# oresat-proto-card.net
KiCad netlist of a schematic drawn in EAGLE
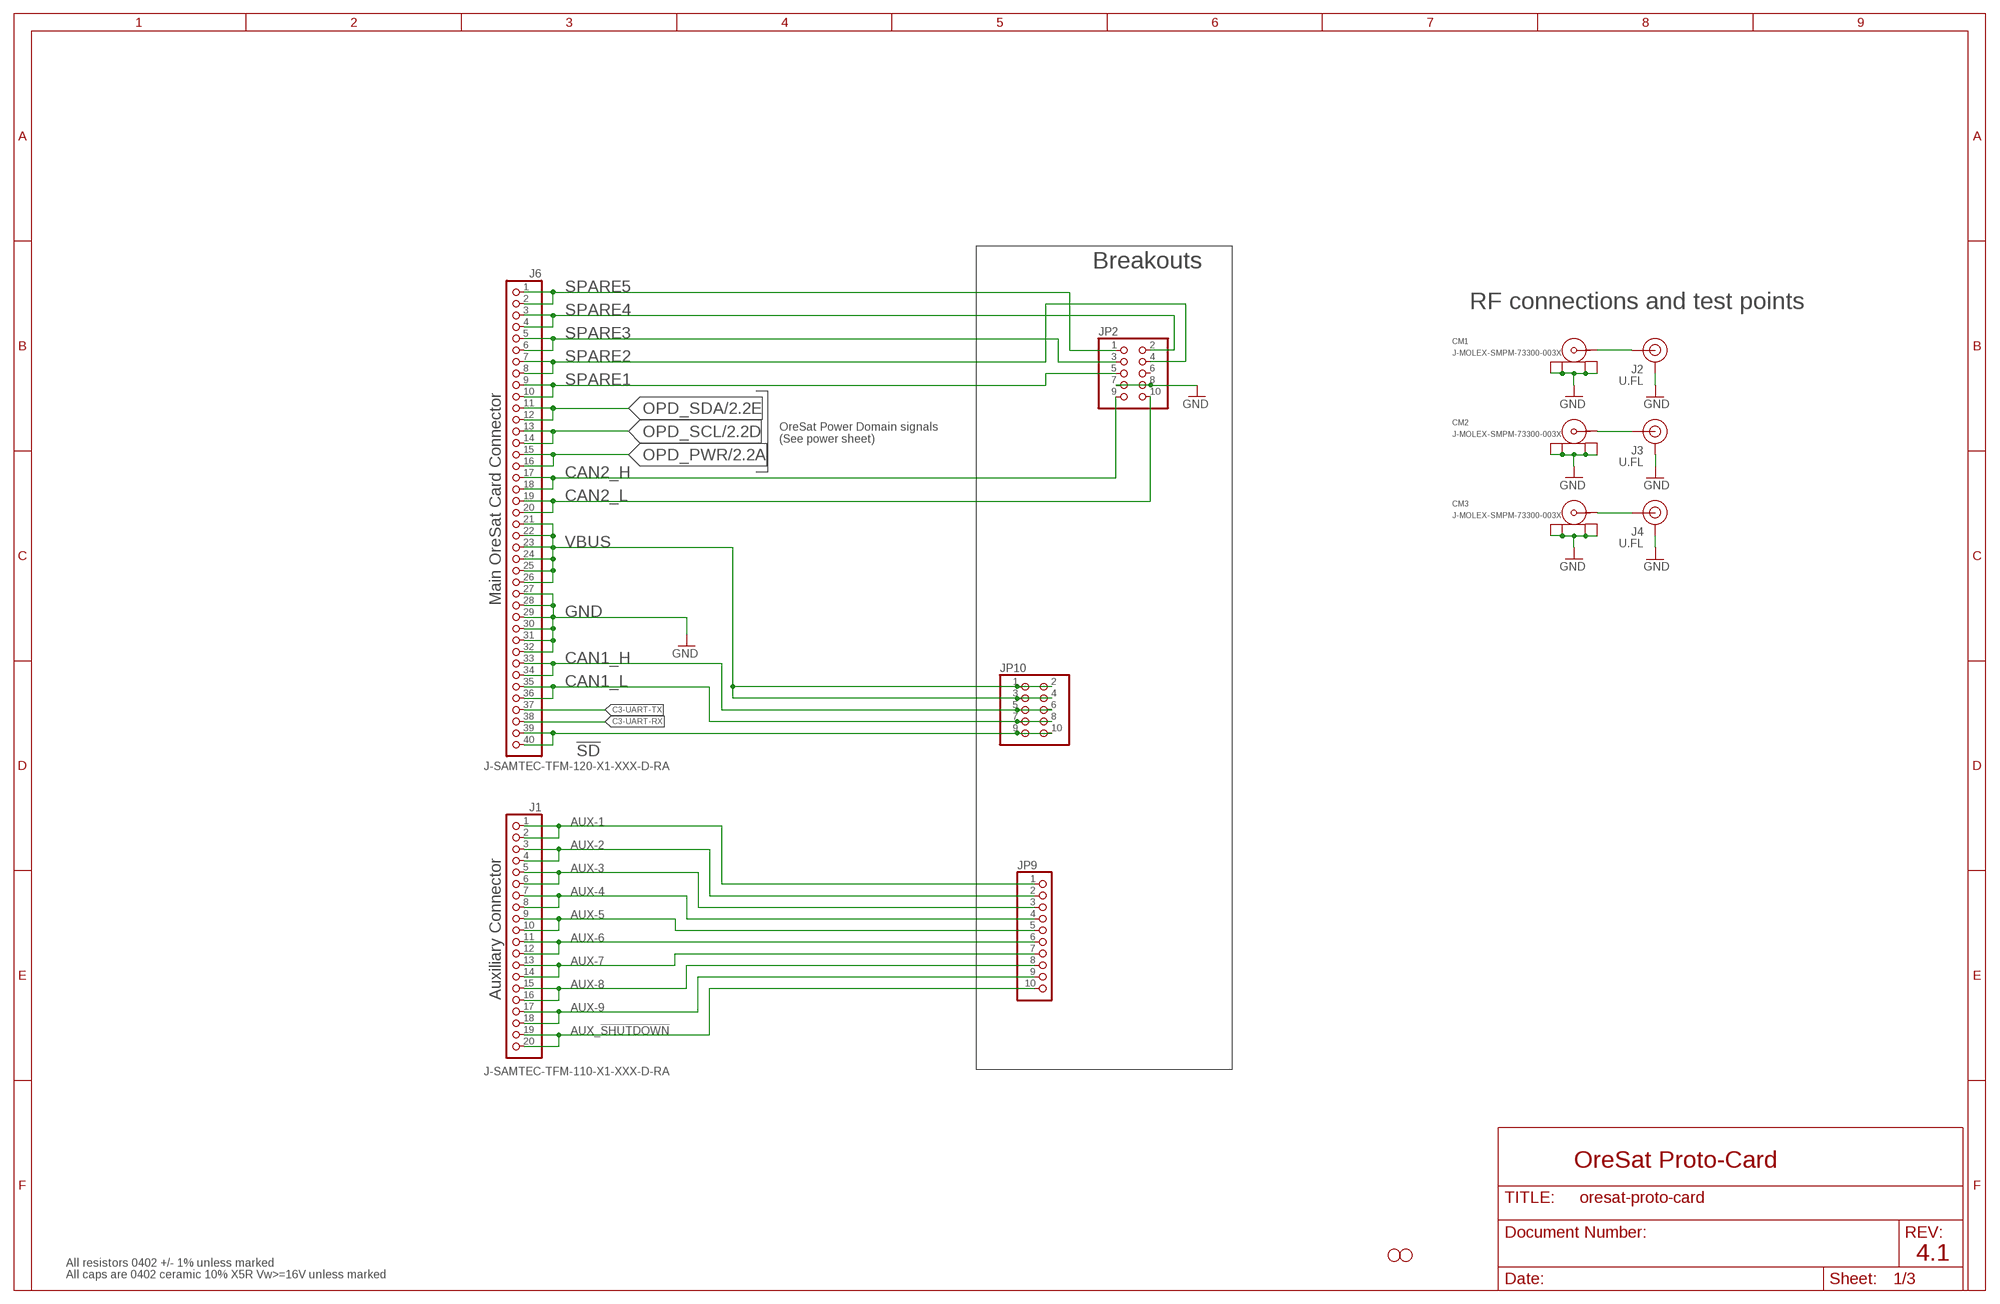
[diagram p0: schematic, sheet 1]
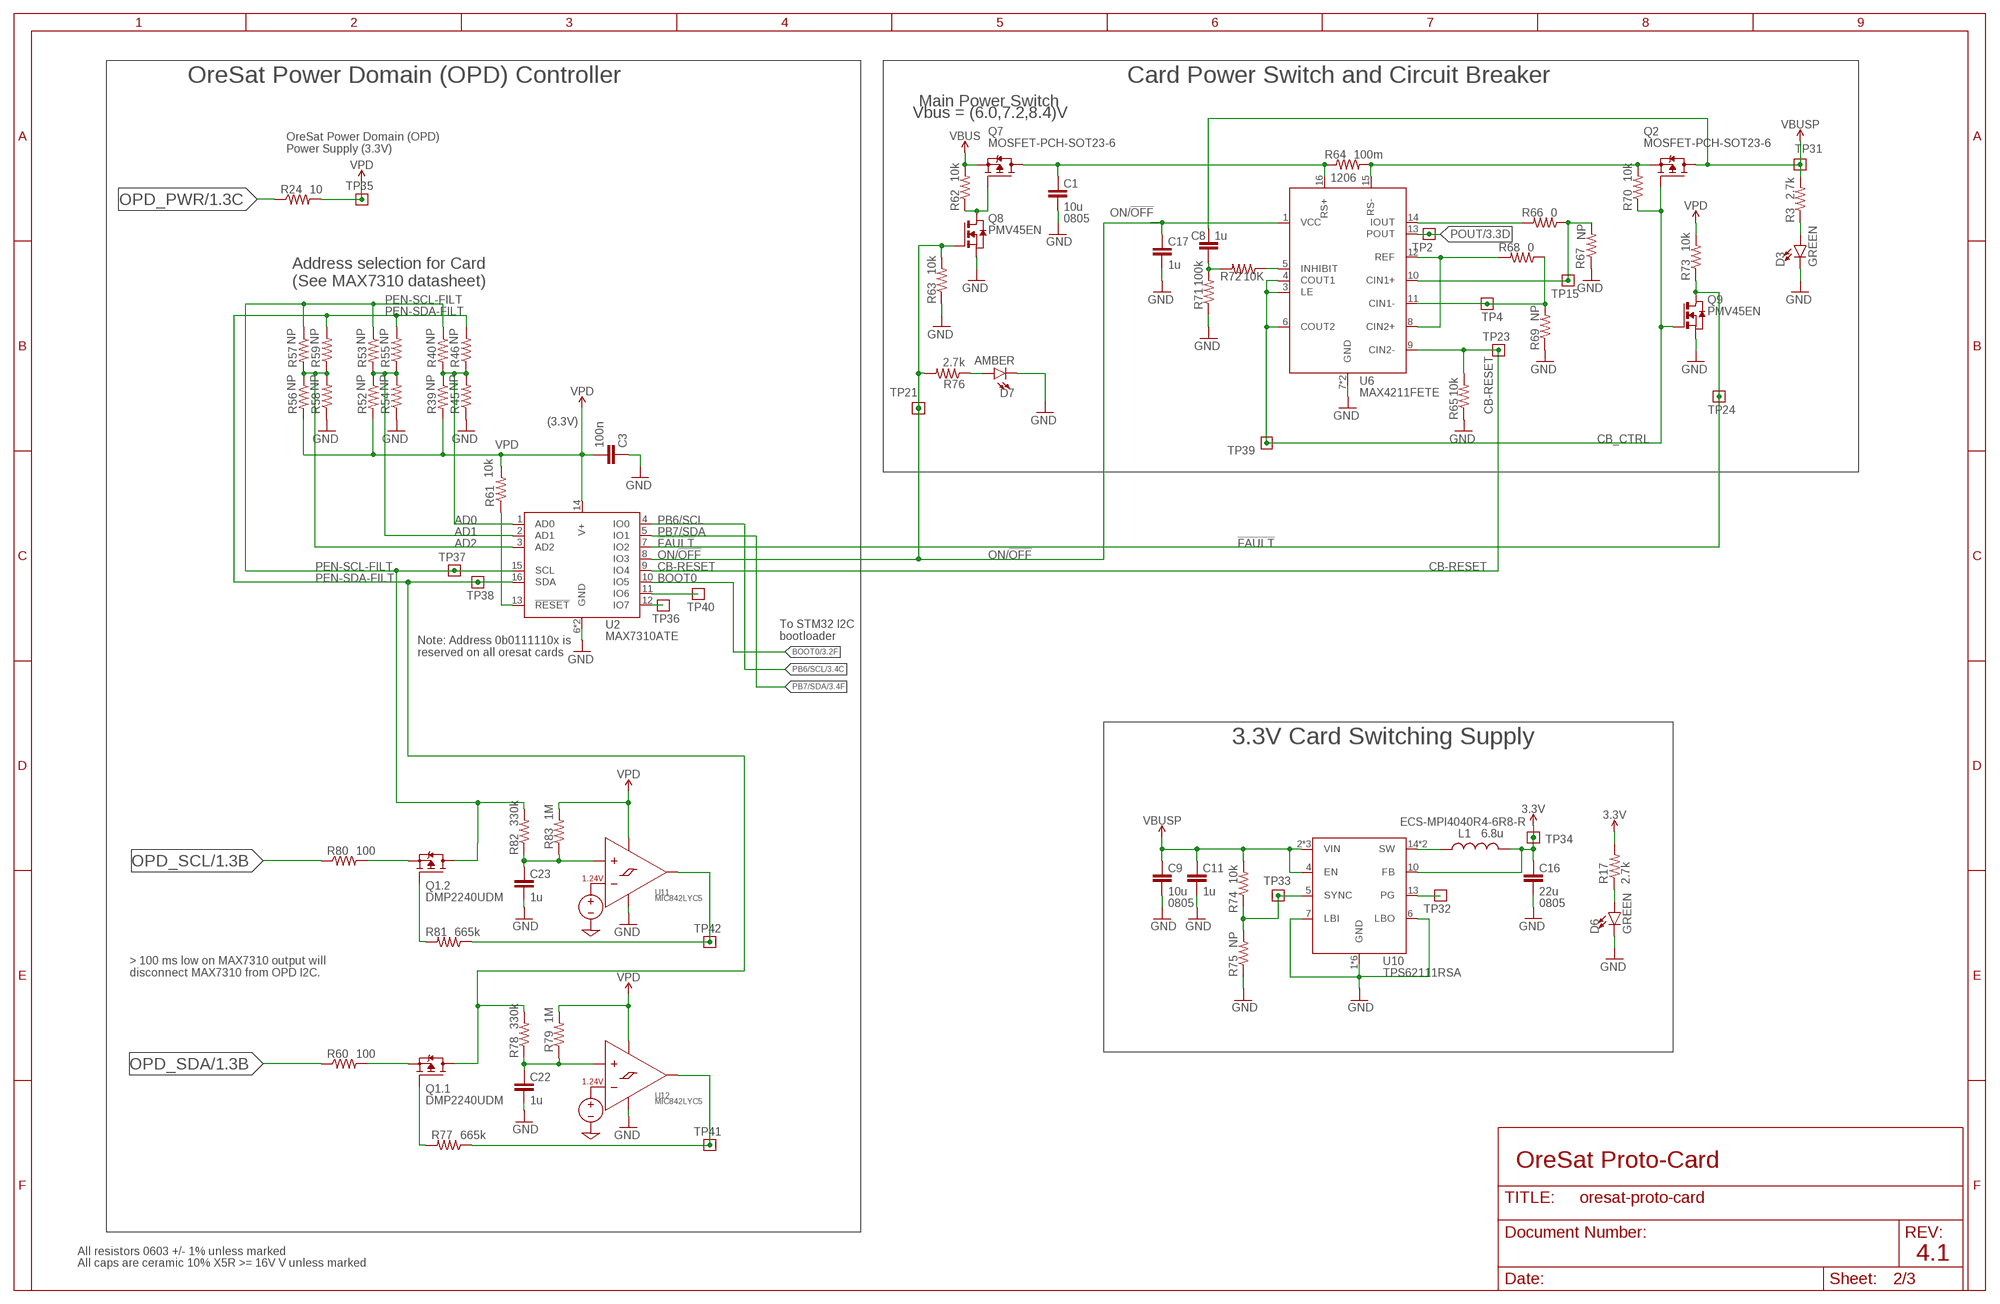
[diagram p1: schematic, sheet 2]
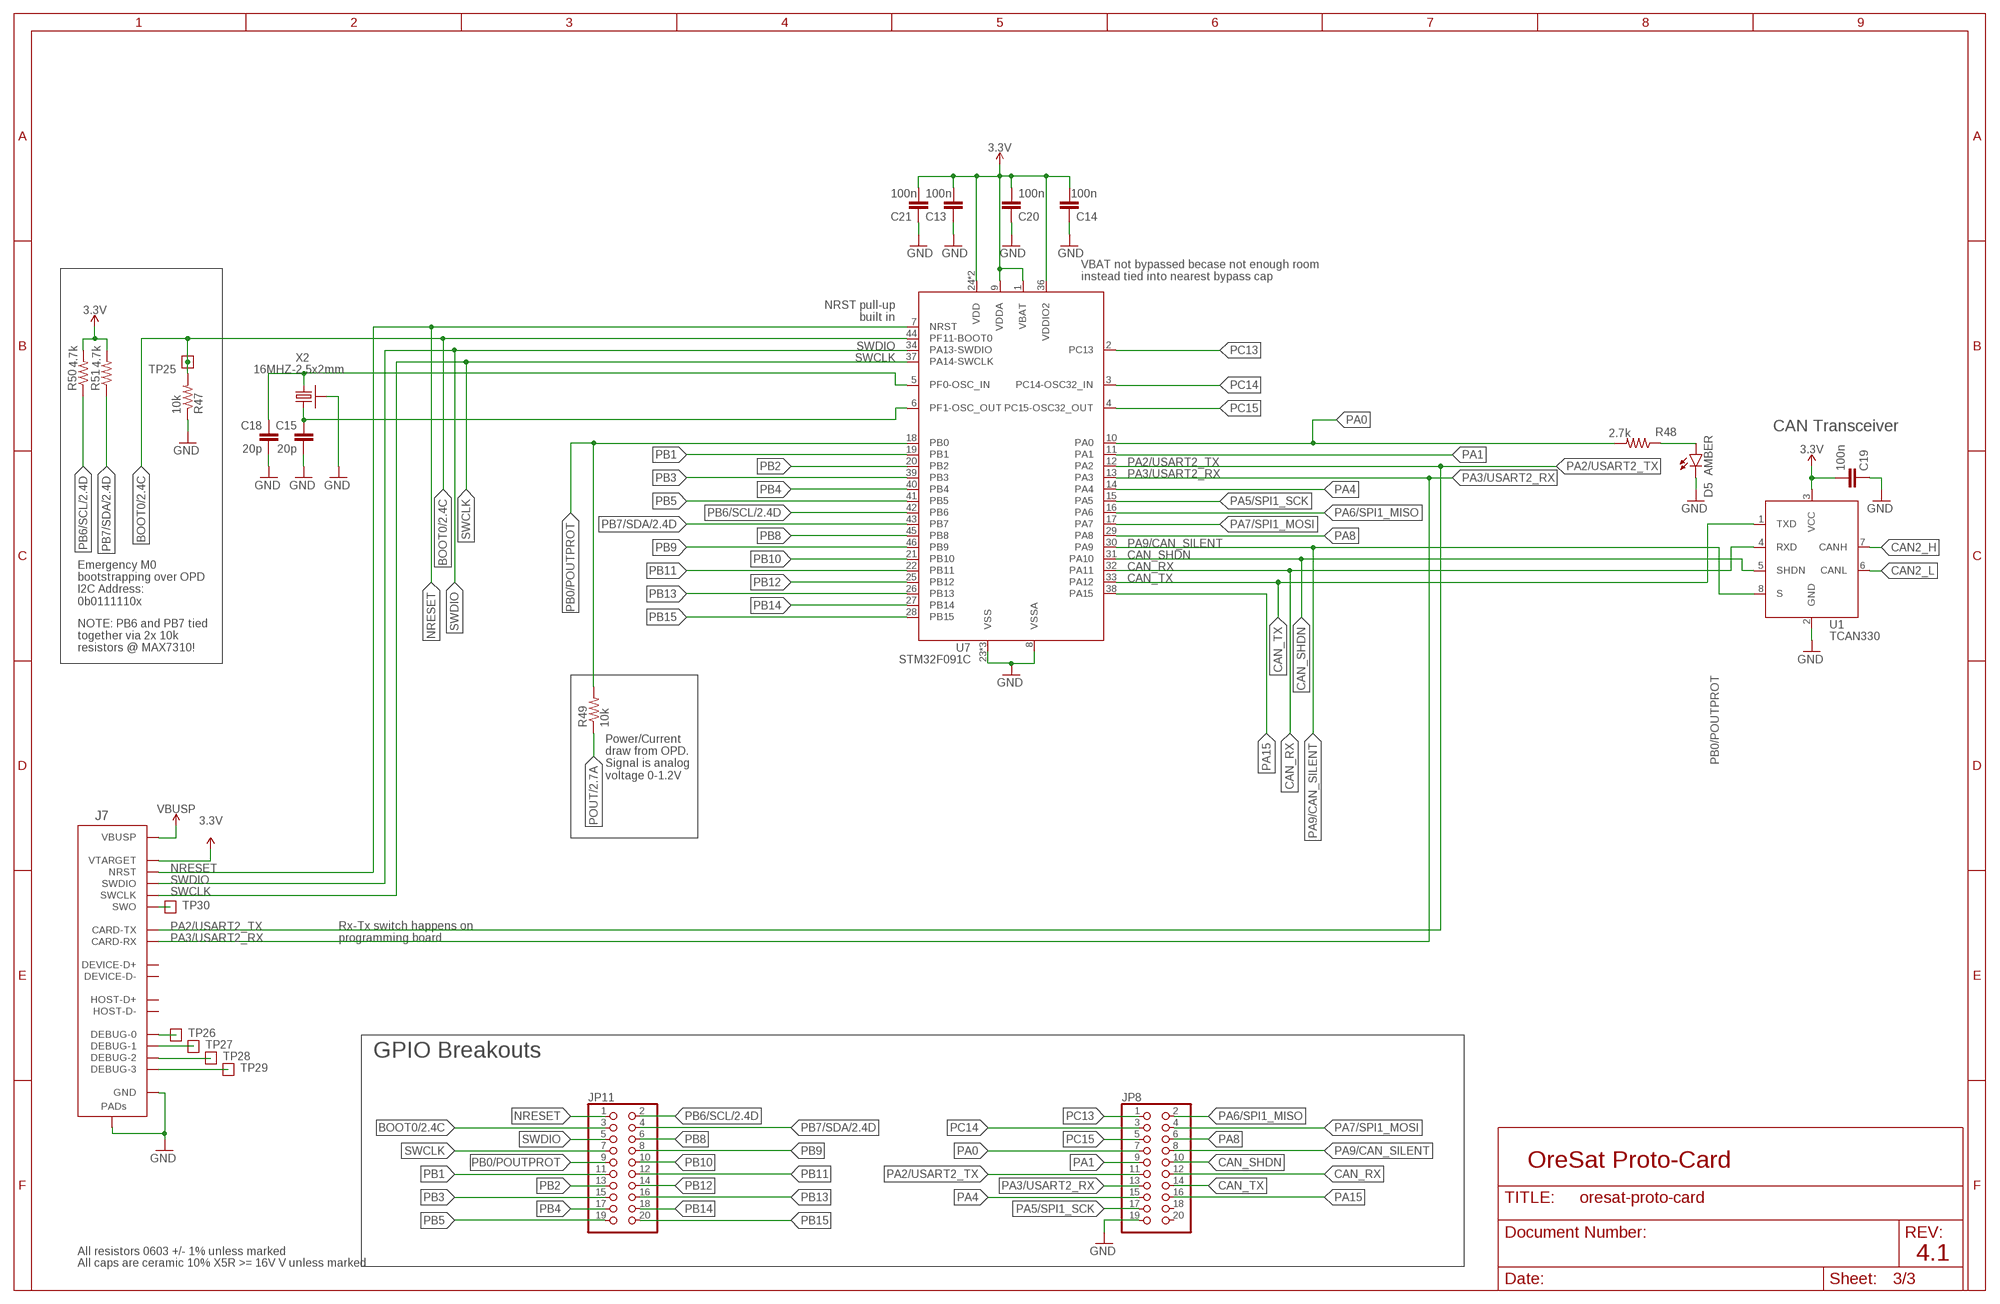
[diagram p2: schematic, sheet 3]

(export (version "E")
  (design (tool "Eeschema 10.0.6"))
  (components
    (comp (ref "CM1")
      (value "J-MOLEX-SMPM-73300-003X")
      (footprint "eagle-import:J-MOLEX-SMPM-073300-003X")
      (fields (field (name "MFR") "Molex") (field (name "MPN") "73300-0020"))
      (libsource (lib "eagle-import") (part "J-MOLEX-SMPM-73300-003X"))
    )
    (comp (ref "CM2")
      (value "J-MOLEX-SMPM-73300-003X")
      (footprint "eagle-import:J-MOLEX-SMPM-073300-003X")
      (fields (field (name "MFR") "Molex") (field (name "MPN") "73300-0020"))
      (libsource (lib "eagle-import") (part "J-MOLEX-SMPM-73300-003X"))
    )
    (comp (ref "CM3")
      (value "J-MOLEX-SMPM-73300-003X")
      (footprint "eagle-import:J-MOLEX-SMPM-073300-003X")
      (fields (field (name "MFR") "Molex") (field (name "MPN") "73300-0020"))
      (libsource (lib "eagle-import") (part "J-MOLEX-SMPM-73300-003X"))
    )
    (comp (ref "H2")
      (value "STAND-OFFTIGHT")
      (footprint "eagle-import:STAND-OFF-TIGHT")
      (libsource (lib "eagle-import") (part "STAND-OFFTIGHT"))
    )
    (comp (ref "H3")
      (value "STAND-OFFTIGHT")
      (footprint "eagle-import:STAND-OFF-TIGHT")
      (libsource (lib "eagle-import") (part "STAND-OFFTIGHT"))
    )
    (comp (ref "J1")
      (value "J-SAMTEC-TFM-110-X1-XXX-D-RA")
      (footprint "eagle-import:J-SAMTEC-TFM-110-X1-XXX-D-RA")
      (fields (field (name "MFR") "Samtec") (field (name "MPN") "TFM-110-01-L-D-RA "))
      (libsource (lib "eagle-import") (part "J-SAMTEC-TFM-110-X1-XXX-D-RA"))
    )
    (comp (ref "J2")
      (value "U.FL")
      (footprint "eagle-import:U.FL")
      (fields (field (name "MFR") "TE Connectivity") (field (name "MPN") "1909763-1"))
      (libsource (lib "eagle-import") (part "U.FL2PIN"))
    )
    (comp (ref "J3")
      (value "U.FL")
      (footprint "eagle-import:U.FL")
      (fields (field (name "MFR") "TE Connectivity") (field (name "MPN") "1909763-1"))
      (libsource (lib "eagle-import") (part "U.FL2PIN"))
    )
    (comp (ref "J4")
      (value "U.FL")
      (footprint "eagle-import:U.FL")
      (fields (field (name "MFR") "TE Connectivity") (field (name "MPN") "1909763-1"))
      (libsource (lib "eagle-import") (part "U.FL2PIN"))
    )
    (comp (ref "J6")
      (value "J-SAMTEC-TFM-120-X1-XXX-D-RA")
      (footprint "eagle-import:J-SAMTEC-TFM-120-X1-XXX-D-RA")
      (fields (field (name "MFR") "Samtec") (field (name "MPN") "TFM-120-01-L-D-RA"))
      (libsource (lib "eagle-import") (part "J-SAMTEC-TFM-120-X1-XXX-D-RA"))
    )
    (comp (ref "JP2")
      (value "PINHD-2X5")
      (footprint "eagle-import:2X05")
      (fields (field (name "MFR") "Amphenol ") (field (name "MPN") "67997-410HLF"))
      (libsource (lib "eagle-import") (part "PINHD-2X5"))
    )
    (comp (ref "JP9")
      (value "PINHD-1X10")
      (footprint "eagle-import:1X10")
      (fields (field (name "MFR") "Wurth") (field (name "MPN") "61302011121"))
      (libsource (lib "eagle-import") (part "PINHD-1X10"))
    )
    (comp (ref "JP10")
      (value "PINHD-2X5")
      (footprint "eagle-import:2X05")
      (fields (field (name "MFR") "Amphenol") (field (name "MPN") "67997-410HLF"))
      (libsource (lib "eagle-import") (part "PINHD-2X5"))
    )
    (comp (ref "C13")
      (value "100n")
      (footprint "eagle-import:.0603-C-NOSILK")
      (fields (field (name "MFR") "Samsung") (field (name "MPN") "CL05B104KO5NNNC"))
      (libsource (lib "eagle-import") (part "C-EU0603-C-NOSILK"))
    )
    (comp (ref "C14")
      (value "100n")
      (footprint "eagle-import:.0603-C-NOSILK")
      (fields (field (name "MFR") "Samsung") (field (name "MPN") "CL05B104KO5NNNC"))
      (libsource (lib "eagle-import") (part "C-EU0603-C-NOSILK"))
    )
    (comp (ref "C15")
      (value "20p")
      (footprint "eagle-import:.0603-C-NOSILK")
      (fields (field (name "MFR") "Samsung") (field (name "MPN") "CL05C200JB51PNC"))
      (libsource (lib "eagle-import") (part "C-EU0603-C-NOSILK"))
    )
    (comp (ref "C18")
      (value "20p")
      (footprint "eagle-import:.0603-C-NOSILK")
      (fields (field (name "MFR") "Samsung") (field (name "MPN") "CL05C200JB51PNC"))
      (libsource (lib "eagle-import") (part "C-EU0603-C-NOSILK"))
    )
    (comp (ref "C19")
      (value "100n")
      (footprint "eagle-import:.0603-C-NOSILK")
      (fields (field (name "MFR") "Samsung") (field (name "MPN") "CL05B104KO5NNNC"))
      (libsource (lib "eagle-import") (part "C-EU0603-C-NOSILK"))
    )
    (comp (ref "C20")
      (value "100n")
      (footprint "eagle-import:.0603-C-NOSILK")
      (fields (field (name "MFR") "Samsung") (field (name "MPN") "CL05B104KO5NNNC"))
      (libsource (lib "eagle-import") (part "C-EU0603-C-NOSILK"))
    )
    (comp (ref "C21")
      (value "100n")
      (footprint "eagle-import:.0603-C-NOSILK")
      (fields (field (name "MFR") "Samsung") (field (name "MPN") "CL05B104KO5NNNC"))
      (libsource (lib "eagle-import") (part "C-EU0603-C-NOSILK"))
    )
    (comp (ref "D5")
      (value "AMBER")
      (footprint "eagle-import:LED-0603")
      (fields (field (name "MFR") "Inolux") (field (name "MPN") "IN-S63AT5A"))
      (libsource (lib "eagle-import") (part "LED-GREEN0603"))
    )
    (comp (ref "J7")
      (value "ORESAT-DEBUG-CONNECTOR-ALL")
      (footprint "eagle-import:TE_2-1734592-0")
      (libsource (lib "eagle-import") (part "ORESAT-DEBUG-CONNECTOR-ALL"))
    )
    (comp (ref "JP8")
      (value "PINHD-2X10")
      (footprint "eagle-import:2X10")
      (fields (field (name "MFR") "Amphenol") (field (name "MPN") "67996-420HLF"))
      (libsource (lib "eagle-import") (part "PINHD-2X10"))
    )
    (comp (ref "JP11")
      (value "PINHD-2X10")
      (footprint "eagle-import:2X10")
      (fields (field (name "MFR") "Amphenol") (field (name "MPN") "67996-420HLF"))
      (libsource (lib "eagle-import") (part "PINHD-2X10"))
    )
    (comp (ref "R47")
      (value "10k")
      (footprint "eagle-import:.0603-C-NOSILK")
      (fields (field (name "MFR") "Yageo") (field (name "MPN") "RC0402FR-0710KL"))
      (libsource (lib "eagle-import") (part "R-US_0603-C-NOSILK"))
    )
    (comp (ref "R48")
      (value "2.7k")
      (footprint "eagle-import:.0603-C-NOSILK")
      (fields (field (name "MFR") "TE Connectivity") (field (name "MPN") "CRGCQ0402F2K7"))
      (libsource (lib "eagle-import") (part "R-US_0603-C-NOSILK"))
    )
    (comp (ref "R49")
      (value "10k")
      (footprint "eagle-import:.0603-C-NOSILK")
      (fields (field (name "MFR") "Yageo") (field (name "MPN") "RC0402FR-0710KL"))
      (libsource (lib "eagle-import") (part "R-US_0603-C-NOSILK"))
    )
    (comp (ref "R50")
      (value "4.7k")
      (footprint "eagle-import:.0603-C-NOSILK")
      (fields (field (name "MFR") "TE Connectivity") (field (name "MPN") "CRGCQ0402F2K7"))
      (libsource (lib "eagle-import") (part "R-US_0603-C-NOSILK"))
    )
    (comp (ref "R51")
      (value "4.7k")
      (footprint "eagle-import:.0603-C-NOSILK")
      (fields (field (name "MFR") "TE Connectivity") (field (name "MPN") "CRGCQ0402F2K7"))
      (libsource (lib "eagle-import") (part "R-US_0603-C-NOSILK"))
    )
    (comp (ref "TP25")
      (value "TEST-POINT-LARGE-SQUARE")
      (footprint "eagle-import:1X01")
      (libsource (lib "eagle-import") (part "TEST-POINT-LARGE-SQUARE"))
    )
    (comp (ref "TP26")
      (value "TEST-POINT-LARGE-SQUARE")
      (footprint "eagle-import:1X01")
      (libsource (lib "eagle-import") (part "TEST-POINT-LARGE-SQUARE"))
    )
    (comp (ref "TP27")
      (value "TEST-POINT-LARGE-SQUARE")
      (footprint "eagle-import:1X01")
      (libsource (lib "eagle-import") (part "TEST-POINT-LARGE-SQUARE"))
    )
    (comp (ref "TP28")
      (value "TEST-POINT-LARGE-SQUARE")
      (footprint "eagle-import:1X01")
      (libsource (lib "eagle-import") (part "TEST-POINT-LARGE-SQUARE"))
    )
    (comp (ref "TP29")
      (value "TEST-POINT-LARGE-SQUARE")
      (footprint "eagle-import:1X01")
      (libsource (lib "eagle-import") (part "TEST-POINT-LARGE-SQUARE"))
    )
    (comp (ref "TP30")
      (value "TEST-POINT-LARGE-SQUARE")
      (footprint "eagle-import:1X01")
      (libsource (lib "eagle-import") (part "TEST-POINT-LARGE-SQUARE"))
    )
    (comp (ref "U1")
      (value "TCAN330")
      (footprint "eagle-import:SOT23-8_TI-DCN")
      (fields (field (name "MFR") "Texas Instruments") (field (name "MPN") "TCAN330GDCNT"))
      (libsource (lib "eagle-import") (part "TCAN330"))
    )
    (comp (ref "U7")
      (value "STM32F091C")
      (footprint "eagle-import:STM32F091C")
      (fields (field (name "MFR") "STMicroelectronics") (field (name "MPN") "STM32F042K6T7"))
      (libsource (lib "eagle-import") (part "STM32F091C"))
    )
    (comp (ref "X2")
      (value "16MHZ-2.5x2mm")
      (footprint "eagle-import:CRYSTAL_2.5X2")
      (fields (field (name "MFR") "ECS Inc.") (field (name "MPN") "ECS-160-10-36Q-ES-TR"))
      (libsource (lib "eagle-import") (part "CRYSTAL-WITH-GND"))
    )
    (comp (ref "C1")
      (value "10u")
      (footprint "eagle-import:.0805-B-NOSILK")
      (fields (field (name "MFR") "Samsung") (field (name "MPN") "CL21B106KOQNNNG"))
      (libsource (lib "eagle-import") (part "C-EU0805-B-NOSILK"))
    )
    (comp (ref "C3")
      (value "100n")
      (footprint "eagle-import:.0603-C-NOSILK")
      (fields (field (name "MFR") "Kemet") (field (name "MPN") "C0603C104K4PAC7867"))
      (libsource (lib "eagle-import") (part "C-EU0603-C-NOSILK"))
    )
    (comp (ref "C8")
      (value "1u")
      (footprint "eagle-import:.0603-C-NOSILK")
      (libsource (lib "eagle-import") (part "C-EU0603-C-NOSILK"))
    )
    (comp (ref "C9")
      (value "10u")
      (footprint "eagle-import:.0805-B-NOSILK")
      (fields (field (name "MFR") "Samsung") (field (name "MPN") "CL21B106KOQNNNG"))
      (libsource (lib "eagle-import") (part "C-EU0805-B-NOSILK"))
    )
    (comp (ref "C11")
      (value "1u")
      (footprint "eagle-import:.0603-C-NOSILK")
      (fields (field (name "MFR") "Yageo") (field (name "MPN") "CC0603KRX5R7BB105"))
      (libsource (lib "eagle-import") (part "C-EU0603-C-NOSILK"))
    )
    (comp (ref "C16")
      (value "22u")
      (footprint "eagle-import:.0805-B-NOSILK")
      (fields (field (name "MFR") "Murata") (field (name "MPN") "GRM21BD71A226ME44L"))
      (libsource (lib "eagle-import") (part "C-EU0805-B-NOSILK"))
    )
    (comp (ref "C17")
      (value "1u")
      (footprint "eagle-import:.0603-C-NOSILK")
      (fields (field (name "MFR") "Yageo") (field (name "MPN") "CC0603KRX5R7BB105"))
      (libsource (lib "eagle-import") (part "C-EU0603-C-NOSILK"))
    )
    (comp (ref "C22")
      (value "1u")
      (footprint "eagle-import:.0603-C-NOSILK")
      (fields (field (name "MFR") "Yageo") (field (name "MPN") "CC0603KRX5R7BB105"))
      (libsource (lib "eagle-import") (part "C-EU0603-C-NOSILK"))
    )
    (comp (ref "C23")
      (value "1u")
      (footprint "eagle-import:.0603-C-NOSILK")
      (fields (field (name "MFR") "Yageo") (field (name "MPN") "CC0603KRX5R7BB105"))
      (libsource (lib "eagle-import") (part "C-EU0603-C-NOSILK"))
    )
    (comp (ref "D3")
      (value "GREEN")
      (footprint "eagle-import:LED-0603")
      (fields (field (name "MFR") "Rohm") (field (name "MPN") "SML-E12M8WT86"))
      (libsource (lib "eagle-import") (part "LED-GREEN0603"))
    )
    (comp (ref "D6")
      (value "GREEN")
      (footprint "eagle-import:LED-0603")
      (fields (field (name "MFR") "Rohm") (field (name "MPN") "SML-E12M8WT86"))
      (libsource (lib "eagle-import") (part "LED-GREEN0603"))
    )
    (comp (ref "D7")
      (value "AMBER")
      (footprint "eagle-import:LED-0603")
      (fields (field (name "MFR") "Inolux") (field (name "MPN") "IN-S63AT5A"))
      (libsource (lib "eagle-import") (part "LED-GREEN0603"))
    )
    (comp (ref "L1")
      (value "6.8u")
      (footprint "eagle-import:ECS-MPI4040")
      (fields (field (name "MFR") "ECS") (field (name "MPN") "ECS-MPI4040R4-6R8-R"))
      (libsource (lib "eagle-import") (part "L-ECS-MPI4040"))
    )
    (comp (ref "Q1")
      (value "DMP2240UDM")
      (footprint "eagle-import:SOT23-6")
      (fields
        (field (name "MFR") "Diodes Inc")
        (field (name "MPN") "DMP2240UDM")
        (field (name "DIS") "Digi-Key")
        (field (name "DPN") "DMP2240UDMDICT-ND")
      )
      (libsource (lib "eagle-import") (part "Q-MOSFET-PCH-dual-SOT23-6_MOSFET-PCH-SOT23-6"))
    )
    (comp (ref "Q2")
      (value "MOSFET-PCH-SOT23-6")
      (footprint "eagle-import:SOT23-6")
      (fields (field (name "MFR") "Diodes Inc") (field (name "MPN") "DMP3050LVT-7"))
      (libsource (lib "eagle-import") (part "MOSFET-PCH-SOT23-6"))
    )
    (comp (ref "Q7")
      (value "MOSFET-PCH-SOT23-6")
      (footprint "eagle-import:SOT23-6")
      (fields (field (name "MFR") "Diodes Inc") (field (name "MPN") "DMP3050LVT-7"))
      (libsource (lib "eagle-import") (part "MOSFET-PCH-SOT23-6"))
    )
    (comp (ref "Q8")
      (value "PMV45EN")
      (footprint "eagle-import:SOT23")
      (fields (field (name "MFR") "Nexperia") (field (name "MPN") "PMV45EN2R"))
      (libsource (lib "eagle-import") (part "PMV45EN"))
    )
    (comp (ref "Q9")
      (value "PMV45EN")
      (footprint "eagle-import:SOT23")
      (fields (field (name "MFR") "Nexperia") (field (name "MPN") "PMV45EN2R"))
      (libsource (lib "eagle-import") (part "PMV45EN"))
    )
    (comp (ref "R3")
      (value "2.7k")
      (footprint "eagle-import:.0603-C-NOSILK")
      (fields (field (name "MFR") "Panasonic") (field (name "MPN") "ERA-3AEB272V"))
      (libsource (lib "eagle-import") (part "R-US_0603-C-NOSILK"))
    )
    (comp (ref "R17")
      (value "2.7k")
      (footprint "eagle-import:.0603-C-NOSILK")
      (fields (field (name "MFR") "Panasonic") (field (name "MPN") "ERA-3AEB272V"))
      (libsource (lib "eagle-import") (part "R-US_0603-C-NOSILK"))
    )
    (comp (ref "R24")
      (value "10")
      (footprint "eagle-import:.0603-C-NOSILK")
      (fields (field (name "MFR") "Yageo") (field (name "MPN") "RC0603FR-0710RL"))
      (libsource (lib "eagle-import") (part "R-US_0603-C-NOSILK"))
    )
    (comp (ref "R39")
      (value "NP")
      (footprint "eagle-import:.0603-C-NOSILK")
      (fields (field (name "MFR") "Samsung") (field (name "MPN") "RC1005F6653CS"))
      (libsource (lib "eagle-import") (part "R-US_0603-C-NOSILK"))
    )
    (comp (ref "R40")
      (value "NP")
      (footprint "eagle-import:.0603-C-NOSILK")
      (fields (field (name "MFR") "Samsung") (field (name "MPN") "RC1005F6653CS"))
      (libsource (lib "eagle-import") (part "R-US_0603-C-NOSILK"))
    )
    (comp (ref "R45")
      (value "NP")
      (footprint "eagle-import:.0603-C-NOSILK")
      (fields (field (name "MFR") "Samsung") (field (name "MPN") "RC1005F6653CS"))
      (libsource (lib "eagle-import") (part "R-US_0603-C-NOSILK"))
    )
    (comp (ref "R46")
      (value "NP")
      (footprint "eagle-import:.0603-C-NOSILK")
      (fields (field (name "MFR") "Samsung") (field (name "MPN") "RC1005F6653CS"))
      (libsource (lib "eagle-import") (part "R-US_0603-C-NOSILK"))
    )
    (comp (ref "R52")
      (value "NP")
      (footprint "eagle-import:.0603-C-NOSILK")
      (fields (field (name "MFR") "Samsung") (field (name "MPN") "RC1005F6653CS"))
      (libsource (lib "eagle-import") (part "R-US_0603-C-NOSILK"))
    )
    (comp (ref "R53")
      (value "NP")
      (footprint "eagle-import:.0603-C-NOSILK")
      (fields (field (name "MFR") "Samsung") (field (name "MPN") "RC1005F6653CS"))
      (libsource (lib "eagle-import") (part "R-US_0603-C-NOSILK"))
    )
    (comp (ref "R54")
      (value "NP")
      (footprint "eagle-import:.0603-C-NOSILK")
      (fields (field (name "MFR") "Samsung") (field (name "MPN") "RC1005F6653CS"))
      (libsource (lib "eagle-import") (part "R-US_0603-C-NOSILK"))
    )
    (comp (ref "R55")
      (value "NP")
      (footprint "eagle-import:.0603-C-NOSILK")
      (fields (field (name "MFR") "Samsung") (field (name "MPN") "RC1005F6653CS"))
      (libsource (lib "eagle-import") (part "R-US_0603-C-NOSILK"))
    )
    (comp (ref "R56")
      (value "NP")
      (footprint "eagle-import:.0603-C-NOSILK")
      (fields (field (name "MFR") "Samsung") (field (name "MPN") "RC1005F6653CS"))
      (libsource (lib "eagle-import") (part "R-US_0603-C-NOSILK"))
    )
    (comp (ref "R57")
      (value "NP")
      (footprint "eagle-import:.0603-C-NOSILK")
      (fields (field (name "MFR") "Samsung") (field (name "MPN") "RC1005F6653CS"))
      (libsource (lib "eagle-import") (part "R-US_0603-C-NOSILK"))
    )
    (comp (ref "R58")
      (value "NP")
      (footprint "eagle-import:.0603-C-NOSILK")
      (fields (field (name "MFR") "Samsung") (field (name "MPN") "RC1005F6653CS"))
      (libsource (lib "eagle-import") (part "R-US_0603-C-NOSILK"))
    )
    (comp (ref "R59")
      (value "NP")
      (footprint "eagle-import:.0603-C-NOSILK")
      (fields (field (name "MFR") "Samsung") (field (name "MPN") "RC1005F6653CS"))
      (libsource (lib "eagle-import") (part "R-US_0603-C-NOSILK"))
    )
    (comp (ref "R60")
      (value "100")
      (footprint "eagle-import:.0603-C-NOSILK")
      (fields (field (name "MFR") "Yageo") (field (name "MPN") "RC0603FR-07100RL "))
      (libsource (lib "eagle-import") (part "R-US_0603-C-NOSILK"))
    )
    (comp (ref "R61")
      (value "10k")
      (footprint "eagle-import:.0603-C-NOSILK")
      (fields (field (name "MFR") "Stackpole") (field (name "MPN") "RNCP0603FTD10K0"))
      (libsource (lib "eagle-import") (part "R-US_0603-C-NOSILK"))
    )
    (comp (ref "R62")
      (value "10k")
      (footprint "eagle-import:.0603-C-NOSILK")
      (fields (field (name "MFR") "Stackpole") (field (name "MPN") "RNCP0603FTD10K0"))
      (libsource (lib "eagle-import") (part "R-US_0603-C-NOSILK"))
    )
    (comp (ref "R63")
      (value "10k")
      (footprint "eagle-import:.0603-C-NOSILK")
      (fields (field (name "MFR") "Stackpole") (field (name "MPN") "RNCP0603FTD10K0"))
      (libsource (lib "eagle-import") (part "R-US_0603-C-NOSILK"))
    )
    (comp (ref "R64")
      (value "100m")
      (footprint "eagle-import:R1206")
      (fields (field (name "MFR") "Stackpole") (field (name "MPN") "CSR1206FTR100"))
      (libsource (lib "eagle-import") (part "rcl_334_R-US_R1206"))
    )
    (comp (ref "R65")
      (value "10k")
      (footprint "eagle-import:.0603-C-NOSILK")
      (fields (field (name "MFR") "Stackpole") (field (name "MPN") "RNCP0603FTD10K0"))
      (libsource (lib "eagle-import") (part "R-US_0603-C-NOSILK"))
    )
    (comp (ref "R66")
      (value "0")
      (footprint "eagle-import:.0603-C-NOSILK")
      (fields (field (name "MFR") "Yageo") (field (name "MPN") "RC0603JR-070RL"))
      (libsource (lib "eagle-import") (part "R-US_0603-C-NOSILK"))
    )
    (comp (ref "R67")
      (value "NP")
      (footprint "eagle-import:.0603-C-NOSILK")
      (fields (field (name "MFR") "Samsung") (field (name "MPN") "RC1005F6653CS"))
      (libsource (lib "eagle-import") (part "R-US_0603-C-NOSILK"))
    )
    (comp (ref "R68")
      (value "0")
      (footprint "eagle-import:.0603-C-NOSILK")
      (fields (field (name "MFR") "Yageo") (field (name "MPN") "RC0603JR-070RL"))
      (libsource (lib "eagle-import") (part "R-US_0603-C-NOSILK"))
    )
    (comp (ref "R69")
      (value "NP")
      (footprint "eagle-import:.0603-C-NOSILK")
      (fields (field (name "MFR") "Samsung") (field (name "MPN") "RC1005F6653CS"))
      (libsource (lib "eagle-import") (part "R-US_0603-C-NOSILK"))
    )
    (comp (ref "R70")
      (value "10k")
      (footprint "eagle-import:.0603-C-NOSILK")
      (fields (field (name "MFR") "Stackpole") (field (name "MPN") "RNCP0603FTD10K0"))
      (libsource (lib "eagle-import") (part "R-US_0603-C-NOSILK"))
    )
    (comp (ref "R71")
      (value "100k")
      (footprint "eagle-import:.0603-C-NOSILK")
      (fields (field (name "MFR") "Samsung") (field (name "MPN") "RC1005F6653CS"))
      (libsource (lib "eagle-import") (part "R-US_0603-C-NOSILK"))
    )
    (comp (ref "R72")
      (value "10K")
      (footprint "eagle-import:.0603-C-NOSILK")
      (fields (field (name "MFR") "Samsung") (field (name "MPN") "RC1005F6653CS"))
      (libsource (lib "eagle-import") (part "R-US_0603-C-NOSILK"))
    )
    (comp (ref "R73")
      (value "10k")
      (footprint "eagle-import:.0603-C-NOSILK")
      (fields (field (name "MFR") "Stackpole") (field (name "MPN") "RNCP0603FTD10K0"))
      (libsource (lib "eagle-import") (part "R-US_0603-C-NOSILK"))
    )
    (comp (ref "R74")
      (value "10k")
      (footprint "eagle-import:.0603-C-NOSILK")
      (fields (field (name "MFR") "Stackpole") (field (name "MPN") "RNCP0603FTD10K0"))
      (libsource (lib "eagle-import") (part "R-US_0603-C-NOSILK"))
    )
    (comp (ref "R75")
      (value "NP")
      (footprint "eagle-import:.0603-C-NOSILK")
      (fields (field (name "MFR") "Samsung") (field (name "MPN") "RC1005F6653CS"))
      (libsource (lib "eagle-import") (part "R-US_0603-C-NOSILK"))
    )
    (comp (ref "R76")
      (value "2.7k")
      (footprint "eagle-import:.0603-C-NOSILK")
      (fields (field (name "MFR") "Panasonic") (field (name "MPN") "ERA-3AEB272V"))
      (libsource (lib "eagle-import") (part "R-US_0603-C-NOSILK"))
    )
    (comp (ref "R77")
      (value "665k")
      (footprint "eagle-import:.0603-C-NOSILK")
      (fields (field (name "MFR") "Stackpole") (field (name "MPN") "RNCP0603FTD10K0"))
      (libsource (lib "eagle-import") (part "R-US_0603-C-NOSILK"))
    )
    (comp (ref "R78")
      (value "330k")
      (footprint "eagle-import:.0603-C-NOSILK")
      (fields (field (name "MFR") "TE Connectivity") (field (name "MPN") "CRGCQ0603F330K"))
      (libsource (lib "eagle-import") (part "R-US_0603-C-NOSILK"))
    )
    (comp (ref "R79")
      (value "1M")
      (footprint "eagle-import:.0603-C-NOSILK")
      (fields (field (name "MFR") "Yageo") (field (name "MPN") "RC0603FR-071ML"))
      (libsource (lib "eagle-import") (part "R-US_0603-C-NOSILK"))
    )
    (comp (ref "R80")
      (value "100")
      (footprint "eagle-import:.0603-C-NOSILK")
      (fields (field (name "MFR") "Yageo") (field (name "MPN") "RC0603FR-07100RL "))
      (libsource (lib "eagle-import") (part "R-US_0603-C-NOSILK"))
    )
    (comp (ref "R81")
      (value "665k")
      (footprint "eagle-import:.0603-C-NOSILK")
      (fields (field (name "MFR") "Stackpole") (field (name "MPN") "RNCP0603FTD10K0"))
      (libsource (lib "eagle-import") (part "R-US_0603-C-NOSILK"))
    )
    (comp (ref "R82")
      (value "330k")
      (footprint "eagle-import:.0603-C-NOSILK")
      (fields (field (name "MFR") "TE Connectivity") (field (name "MPN") "CRGCQ0603F330K"))
      (libsource (lib "eagle-import") (part "R-US_0603-C-NOSILK"))
    )
    (comp (ref "R83")
      (value "1M")
      (footprint "eagle-import:.0603-C-NOSILK")
      (fields (field (name "MFR") "Yageo") (field (name "MPN") "RC0603FR-071ML"))
      (libsource (lib "eagle-import") (part "R-US_0603-C-NOSILK"))
    )
    (comp (ref "TP2")
      (value "TEST-POINT-LARGE-SQUARE")
      (footprint "eagle-import:1X01")
      (libsource (lib "eagle-import") (part "TEST-POINT-LARGE-SQUARE"))
    )
    (comp (ref "TP4")
      (value "TEST-POINT-LARGE-SQUARE")
      (footprint "eagle-import:1X01")
      (libsource (lib "eagle-import") (part "TEST-POINT-LARGE-SQUARE"))
    )
    (comp (ref "TP15")
      (value "TEST-POINT-LARGE-SQUARE")
      (footprint "eagle-import:1X01")
      (libsource (lib "eagle-import") (part "TEST-POINT-LARGE-SQUARE"))
    )
    (comp (ref "TP21")
      (value "TEST-POINT-LARGE-SQUARE")
      (footprint "eagle-import:1X01")
      (libsource (lib "eagle-import") (part "TEST-POINT-LARGE-SQUARE"))
    )
    (comp (ref "TP23")
      (value "TEST-POINT-LARGE-SQUARE")
      (footprint "eagle-import:1X01")
      (libsource (lib "eagle-import") (part "TEST-POINT-LARGE-SQUARE"))
    )
    (comp (ref "TP24")
      (value "TEST-POINT-LARGE-SQUARE")
      (footprint "eagle-import:1X01")
      (libsource (lib "eagle-import") (part "TEST-POINT-LARGE-SQUARE"))
    )
    (comp (ref "TP31")
      (value "TEST-POINT-LARGE-SQUARE")
      (footprint "eagle-import:1X01")
      (libsource (lib "eagle-import") (part "TEST-POINT-LARGE-SQUARE"))
    )
    (comp (ref "TP32")
      (value "TEST-POINT-LARGE-SQUARE")
      (footprint "eagle-import:1X01")
      (libsource (lib "eagle-import") (part "TEST-POINT-LARGE-SQUARE"))
    )
    (comp (ref "TP33")
      (value "TEST-POINT-LARGE-SQUARE")
      (footprint "eagle-import:1X01")
      (libsource (lib "eagle-import") (part "TEST-POINT-LARGE-SQUARE"))
    )
    (comp (ref "TP34")
      (value "TEST-POINT-LARGE-SQUARE")
      (footprint "eagle-import:1X01")
      (libsource (lib "eagle-import") (part "TEST-POINT-LARGE-SQUARE"))
    )
    (comp (ref "TP35")
      (value "TEST-POINT-LARGE-SQUARE")
      (footprint "eagle-import:1X01")
      (libsource (lib "eagle-import") (part "TEST-POINT-LARGE-SQUARE"))
    )
    (comp (ref "TP36")
      (value "TEST-POINT-LARGE-SQUARE")
      (footprint "eagle-import:1X01")
      (libsource (lib "eagle-import") (part "TEST-POINT-LARGE-SQUARE"))
    )
    (comp (ref "TP37")
      (value "TEST-POINT-LARGE-SQUARE")
      (footprint "eagle-import:1X01")
      (libsource (lib "eagle-import") (part "TEST-POINT-LARGE-SQUARE"))
    )
    (comp (ref "TP38")
      (value "TEST-POINT-LARGE-SQUARE")
      (footprint "eagle-import:1X01")
      (libsource (lib "eagle-import") (part "TEST-POINT-LARGE-SQUARE"))
    )
    (comp (ref "TP39")
      (value "TEST-POINT-LARGE-SQUARE")
      (footprint "eagle-import:1X01")
      (libsource (lib "eagle-import") (part "TEST-POINT-LARGE-SQUARE"))
    )
    (comp (ref "TP40")
      (value "TEST-POINT-LARGE-SQUARE")
      (footprint "eagle-import:1X01")
      (libsource (lib "eagle-import") (part "TEST-POINT-LARGE-SQUARE"))
    )
    (comp (ref "TP41")
      (value "TEST-POINT-LARGE-SQUARE")
      (footprint "eagle-import:1X01")
      (libsource (lib "eagle-import") (part "TEST-POINT-LARGE-SQUARE"))
    )
    (comp (ref "TP42")
      (value "TEST-POINT-LARGE-SQUARE")
      (footprint "eagle-import:1X01")
      (libsource (lib "eagle-import") (part "TEST-POINT-LARGE-SQUARE"))
    )
    (comp (ref "U2")
      (value "MAX7310ATE")
      (footprint "eagle-import:QFN65P400X400X80-17T210")
      (fields (field (name "MFR") "Maxim"))
      (libsource (lib "eagle-import") (part "MAX7310"))
    )
    (comp (ref "U6")
      (value "MAX4211FETE")
      (footprint "eagle-import:QFN65P400X400X80-17T210")
      (fields (field (name "MFR") "Maxim"))
      (libsource (lib "eagle-import") (part "MAX4211"))
    )
    (comp (ref "U10")
      (value "TPS62111RSA")
      (footprint "eagle-import:S-PVQFN-16")
      (fields (field (name "MFR") "Texas Instruments"))
      (libsource (lib "eagle-import") (part "TPS6211X"))
    )
    (comp (ref "U11")
      (value "MIC842LYC5")
      (footprint "eagle-import:SC70-5")
      (libsource (lib "eagle-import") (part "MIC842LYC5"))
    )
    (comp (ref "U12")
      (value "MIC842LYC5")
      (footprint "eagle-import:SC70-5")
      (libsource (lib "eagle-import") (part "MIC842LYC5"))
    )
  )
  (nets
    (net (code "1") (name "3.3V") (class "Default")
      (node (ref "C13") (pin "2") (pinfunction "2_2") (pintype "passive"))
      (node (ref "C14") (pin "2") (pinfunction "2_2") (pintype "passive"))
      (node (ref "C16") (pin "1") (pinfunction "1_1") (pintype "passive"))
      (node (ref "C19") (pin "2") (pinfunction "2_2") (pintype "passive"))
      (node (ref "C20") (pin "2") (pinfunction "2_2") (pintype "passive"))
      (node (ref "C21") (pin "2") (pinfunction "2_2") (pintype "passive"))
      (node (ref "J7") (pin "11") (pinfunction "VTARGET_11") (pintype "passive"))
      (node (ref "L1") (pin "2") (pinfunction "2_2") (pintype "passive"))
      (node (ref "R17") (pin "2") (pinfunction "2_2") (pintype "passive"))
      (node (ref "R50") (pin "2") (pinfunction "2_2") (pintype "passive"))
      (node (ref "R51") (pin "2") (pinfunction "2_2") (pintype "passive"))
      (node (ref "TP34") (pin "1") (pinfunction "1_1") (pintype "passive"))
      (node (ref "U1") (pin "3") (pinfunction "VCC_3") (pintype "power_in"))
      (node (ref "U10") (pin "10") (pinfunction "FB_10") (pintype "input"))
      (node (ref "U7") (pin "1") (pinfunction "VBAT_1") (pintype "power_in"))
      (node (ref "U7") (pin "24") (pinfunction "VDD_24") (pintype "power_in"))
      (node (ref "U7") (pin "36") (pinfunction "VDDIO2_36") (pintype "power_in"))
      (node (ref "U7") (pin "48") (pinfunction "VDD_48") (pintype "power_in"))
      (node (ref "U7") (pin "9") (pinfunction "VDDA_9") (pintype "power_in"))
    )
    (net (code "2") (name "AD0") (class "Default")
      (node (ref "R39") (pin "1") (pinfunction "1_1") (pintype "passive"))
      (node (ref "R40") (pin "2") (pinfunction "2_2") (pintype "passive"))
      (node (ref "R45") (pin "2") (pinfunction "2_2") (pintype "passive"))
      (node (ref "R46") (pin "1") (pinfunction "1_1") (pintype "passive"))
      (node (ref "U2") (pin "1") (pinfunction "AD0_1") (pintype "input"))
    )
    (net (code "3") (name "AD1") (class "Default")
      (node (ref "R52") (pin "1") (pinfunction "1_1") (pintype "passive"))
      (node (ref "R53") (pin "2") (pinfunction "2_2") (pintype "passive"))
      (node (ref "R54") (pin "2") (pinfunction "2_2") (pintype "passive"))
      (node (ref "R55") (pin "1") (pinfunction "1_1") (pintype "passive"))
      (node (ref "U2") (pin "2") (pinfunction "AD1_2") (pintype "input"))
    )
    (net (code "4") (name "AD2") (class "Default")
      (node (ref "R56") (pin "1") (pinfunction "1_1") (pintype "passive"))
      (node (ref "R57") (pin "2") (pinfunction "2_2") (pintype "passive"))
      (node (ref "R58") (pin "2") (pinfunction "2_2") (pintype "passive"))
      (node (ref "R59") (pin "1") (pinfunction "1_1") (pintype "passive"))
      (node (ref "U2") (pin "3") (pinfunction "AD2_3") (pintype "input"))
    )
    (net (code "5") (name "AUX-1") (class "Default")
      (node (ref "J1") (pin "1") (pinfunction "1_1") (pintype "passive"))
      (node (ref "J1") (pin "2") (pinfunction "2_2") (pintype "passive"))
      (node (ref "JP9") (pin "1") (pinfunction "1_1") (pintype "passive"))
    )
    (net (code "6") (name "AUX-2") (class "Default")
      (node (ref "J1") (pin "3") (pinfunction "3_3") (pintype "passive"))
      (node (ref "J1") (pin "4") (pinfunction "4_4") (pintype "passive"))
      (node (ref "JP9") (pin "2") (pinfunction "2_2") (pintype "passive"))
    )
    (net (code "7") (name "AUX-3") (class "Default")
      (node (ref "J1") (pin "5") (pinfunction "5_5") (pintype "passive"))
      (node (ref "J1") (pin "6") (pinfunction "6_6") (pintype "passive"))
      (node (ref "JP9") (pin "3") (pinfunction "3_3") (pintype "passive"))
    )
    (net (code "8") (name "AUX-4") (class "Default")
      (node (ref "J1") (pin "7") (pinfunction "7_7") (pintype "passive"))
      (node (ref "J1") (pin "8") (pinfunction "8_8") (pintype "passive"))
      (node (ref "JP9") (pin "4") (pinfunction "4_4") (pintype "passive"))
    )
    (net (code "9") (name "AUX-5") (class "Default")
      (node (ref "J1") (pin "10") (pinfunction "10_10") (pintype "passive"))
      (node (ref "J1") (pin "9") (pinfunction "9_9") (pintype "passive"))
      (node (ref "JP9") (pin "5") (pinfunction "5_5") (pintype "passive"))
    )
    (net (code "10") (name "AUX-6") (class "Default")
      (node (ref "J1") (pin "11") (pinfunction "11_11") (pintype "passive"))
      (node (ref "J1") (pin "12") (pinfunction "12_12") (pintype "passive"))
      (node (ref "JP9") (pin "6") (pinfunction "6_6") (pintype "passive"))
    )
    (net (code "11") (name "AUX-7") (class "Default")
      (node (ref "J1") (pin "13") (pinfunction "13_13") (pintype "passive"))
      (node (ref "J1") (pin "14") (pinfunction "14_14") (pintype "passive"))
      (node (ref "JP9") (pin "7") (pinfunction "7_7") (pintype "passive"))
    )
    (net (code "12") (name "AUX-8") (class "Default")
      (node (ref "J1") (pin "15") (pinfunction "15_15") (pintype "passive"))
      (node (ref "J1") (pin "16") (pinfunction "16_16") (pintype "passive"))
      (node (ref "JP9") (pin "8") (pinfunction "8_8") (pintype "passive"))
    )
    (net (code "13") (name "AUX-9") (class "Default")
      (node (ref "J1") (pin "17") (pinfunction "17_17") (pintype "passive"))
      (node (ref "J1") (pin "18") (pinfunction "18_18") (pintype "passive"))
      (node (ref "JP9") (pin "9") (pinfunction "9_9") (pintype "passive"))
    )
    (net (code "14") (name "AUX_~{SHUTDOWN}") (class "Default")
      (node (ref "J1") (pin "19") (pinfunction "19_19") (pintype "passive"))
      (node (ref "J1") (pin "20") (pinfunction "20_20") (pintype "passive"))
      (node (ref "JP9") (pin "10") (pinfunction "10_10") (pintype "passive"))
    )
    (net (code "15") (name "BOOT0") (class "Default")
      (node (ref "JP11") (pin "3") (pinfunction "3_3") (pintype "passive"))
      (node (ref "R47") (pin "2") (pinfunction "2_2") (pintype "passive"))
      (node (ref "TP25") (pin "1") (pinfunction "1_1") (pintype "passive"))
      (node (ref "U2") (pin "10") (pinfunction "IO5_10") (pintype "bidirectional"))
      (node (ref "U7") (pin "44") (pinfunction "PF11-BOOT0_44") (pintype "bidirectional"))
    )
    (net (code "16") (name "C3-UART-RX") (class "Default")
      (node (ref "J6") (pin "38") (pinfunction "38_38") (pintype "passive"))
    )
    (net (code "17") (name "C3-UART-TX") (class "Default")
      (node (ref "J6") (pin "37") (pinfunction "37_37") (pintype "passive"))
    )
    (net (code "18") (name "CAN1_H") (class "Default")
      (node (ref "J6") (pin "33") (pinfunction "33_33") (pintype "passive"))
      (node (ref "J6") (pin "34") (pinfunction "34_34") (pintype "passive"))
      (node (ref "JP10") (pin "5") (pinfunction "5_5") (pintype "passive"))
      (node (ref "JP10") (pin "6") (pinfunction "6_6") (pintype "passive"))
    )
    (net (code "19") (name "CAN1_L") (class "Default")
      (node (ref "J6") (pin "35") (pinfunction "35_35") (pintype "passive"))
      (node (ref "J6") (pin "36") (pinfunction "36_36") (pintype "passive"))
      (node (ref "JP10") (pin "7") (pinfunction "7_7") (pintype "passive"))
      (node (ref "JP10") (pin "8") (pinfunction "8_8") (pintype "passive"))
    )
    (net (code "20") (name "CAN2_H") (class "Default")
      (node (ref "J6") (pin "17") (pinfunction "17_17") (pintype "passive"))
      (node (ref "J6") (pin "18") (pinfunction "18_18") (pintype "passive"))
      (node (ref "JP2") (pin "9") (pinfunction "9_9") (pintype "passive"))
      (node (ref "U1") (pin "7") (pinfunction "CANH_7") (pintype "bidirectional"))
    )
    (net (code "21") (name "CAN2_L") (class "Default")
      (node (ref "J6") (pin "19") (pinfunction "19_19") (pintype "passive"))
      (node (ref "J6") (pin "20") (pinfunction "20_20") (pintype "passive"))
      (node (ref "JP2") (pin "10") (pinfunction "10_10") (pintype "passive"))
      (node (ref "U1") (pin "6") (pinfunction "CANL_6") (pintype "bidirectional"))
    )
    (net (code "22") (name "CAN_RX") (class "Default")
      (node (ref "JP8") (pin "12") (pinfunction "12_12") (pintype "passive"))
      (node (ref "U1") (pin "4") (pinfunction "RXD_4") (pintype "output"))
      (node (ref "U7") (pin "32") (pinfunction "PA11_32") (pintype "bidirectional"))
    )
    (net (code "23") (name "CAN_SHDN") (class "Default")
      (node (ref "JP8") (pin "10") (pinfunction "10_10") (pintype "passive"))
      (node (ref "U1") (pin "5") (pinfunction "SHDN_5") (pintype "input"))
      (node (ref "U7") (pin "31") (pinfunction "PA10_31") (pintype "bidirectional"))
    )
    (net (code "24") (name "CAN_TX") (class "Default")
      (node (ref "JP8") (pin "14") (pinfunction "14_14") (pintype "passive"))
      (node (ref "U1") (pin "1") (pinfunction "TXD_1") (pintype "input"))
      (node (ref "U7") (pin "33") (pinfunction "PA12_33") (pintype "bidirectional"))
    )
    (net (code "25") (name "CB-RESET") (class "Default")
      (node (ref "R65") (pin "2") (pinfunction "2_2") (pintype "passive"))
      (node (ref "TP23") (pin "1") (pinfunction "1_1") (pintype "passive"))
      (node (ref "U2") (pin "9") (pinfunction "IO4_9") (pintype "bidirectional"))
      (node (ref "U6") (pin "9") (pinfunction "CIN2-_9") (pintype "input"))
    )
    (net (code "26") (name "CB_CTRL") (class "Default")
      (node (ref "Q2") (pin "3") (pinfunction "G_3") (pintype "passive"))
      (node (ref "Q9") (pin "1") (pinfunction "G_1") (pintype "passive"))
      (node (ref "R70") (pin "1") (pinfunction "1_1") (pintype "passive"))
      (node (ref "TP39") (pin "1") (pinfunction "1_1") (pintype "passive"))
      (node (ref "U6") (pin "3") (pinfunction "LE_3") (pintype "input"))
      (node (ref "U6") (pin "4") (pinfunction "COUT1_4") (pintype "open_collector"))
      (node (ref "U6") (pin "6") (pinfunction "COUT2_6") (pintype "open_collector"))
    )
    (net (code "27") (name "GND") (class "Default")
      (node (ref "C1") (pin "2") (pinfunction "2_2") (pintype "passive"))
      (node (ref "C11") (pin "2") (pinfunction "2_2") (pintype "passive"))
      (node (ref "C13") (pin "1") (pinfunction "1_1") (pintype "passive"))
      (node (ref "C14") (pin "1") (pinfunction "1_1") (pintype "passive"))
      (node (ref "C15") (pin "2") (pinfunction "2_2") (pintype "passive"))
      (node (ref "C16") (pin "2") (pinfunction "2_2") (pintype "passive"))
      (node (ref "C17") (pin "2") (pinfunction "2_2") (pintype "passive"))
      (node (ref "C18") (pin "2") (pinfunction "2_2") (pintype "passive"))
      (node (ref "C19") (pin "1") (pinfunction "1_1") (pintype "passive"))
      (node (ref "C20") (pin "1") (pinfunction "1_1") (pintype "passive"))
      (node (ref "C21") (pin "1") (pinfunction "1_1") (pintype "passive"))
      (node (ref "C22") (pin "2") (pinfunction "2_2") (pintype "passive"))
      (node (ref "C23") (pin "2") (pinfunction "2_2") (pintype "passive"))
      (node (ref "C3") (pin "1") (pinfunction "1_1") (pintype "passive"))
      (node (ref "C9") (pin "2") (pinfunction "2_2") (pintype "passive"))
      (node (ref "CM1") (pin "P$1") (pinfunction "SHIELD3_P$1") (pintype "passive"))
      (node (ref "CM1") (pin "P$2") (pinfunction "SHIELD2_P$2") (pintype "passive"))
      (node (ref "CM1") (pin "P$3") (pinfunction "SHIELD1_P$3") (pintype "passive"))
      (node (ref "CM1") (pin "P$4") (pinfunction "SHIELD_P$4") (pintype "passive"))
      (node (ref "CM2") (pin "P$1") (pinfunction "SHIELD3_P$1") (pintype "passive"))
      (node (ref "CM2") (pin "P$2") (pinfunction "SHIELD2_P$2") (pintype "passive"))
      (node (ref "CM2") (pin "P$3") (pinfunction "SHIELD1_P$3") (pintype "passive"))
      (node (ref "CM2") (pin "P$4") (pinfunction "SHIELD_P$4") (pintype "passive"))
      (node (ref "CM3") (pin "P$1") (pinfunction "SHIELD3_P$1") (pintype "passive"))
      (node (ref "CM3") (pin "P$2") (pinfunction "SHIELD2_P$2") (pintype "passive"))
      (node (ref "CM3") (pin "P$3") (pinfunction "SHIELD1_P$3") (pintype "passive"))
      (node (ref "CM3") (pin "P$4") (pinfunction "SHIELD_P$4") (pintype "passive"))
      (node (ref "D3") (pin "C") (pinfunction "C_C") (pintype "passive"))
      (node (ref "D5") (pin "C") (pinfunction "C_C") (pintype "passive"))
      (node (ref "D6") (pin "C") (pinfunction "C_C") (pintype "passive"))
      (node (ref "D7") (pin "C") (pinfunction "C_C") (pintype "passive"))
      (node (ref "J2") (pin "1") (pinfunction "GND_1") (pintype "bidirectional"))
      (node (ref "J2") (pin "2") (pinfunction "GND_2") (pintype "bidirectional"))
      (node (ref "J3") (pin "1") (pinfunction "GND_1") (pintype "bidirectional"))
      (node (ref "J3") (pin "2") (pinfunction "GND_2") (pintype "bidirectional"))
      (node (ref "J4") (pin "1") (pinfunction "GND_1") (pintype "bidirectional"))
      (node (ref "J4") (pin "2") (pinfunction "GND_2") (pintype "bidirectional"))
      (node (ref "J6") (pin "27") (pinfunction "27_27") (pintype "passive"))
      (node (ref "J6") (pin "28") (pinfunction "28_28") (pintype "passive"))
      (node (ref "J6") (pin "29") (pinfunction "29_29") (pintype "passive"))
      (node (ref "J6") (pin "30") (pinfunction "30_30") (pintype "passive"))
      (node (ref "J6") (pin "31") (pinfunction "31_31") (pintype "passive"))
      (node (ref "J6") (pin "32") (pinfunction "32_32") (pintype "passive"))
      (node (ref "J7") (pin "3") (pinfunction "GND_3") (pintype "passive"))
      (node (ref "J7") (pin "6") (pinfunction "GND_6") (pintype "passive"))
      (node (ref "J7") (pin "9") (pinfunction "GND_9") (pintype "passive"))
      (node (ref "J7") (pin "PAD1") (pinfunction "PAD_PAD1") (pintype "bidirectional"))
      (node (ref "J7") (pin "PAD2") (pinfunction "PAD_PAD2") (pintype "bidirectional"))
      (node (ref "JP2") (pin "7") (pinfunction "7_7") (pintype "passive"))
      (node (ref "JP2") (pin "8") (pinfunction "8_8") (pintype "passive"))
      (node (ref "JP8") (pin "19") (pinfunction "19_19") (pintype "passive"))
      (node (ref "Q8") (pin "2") (pinfunction "S_2") (pintype "passive"))
      (node (ref "Q9") (pin "2") (pinfunction "S_2") (pintype "passive"))
      (node (ref "R45") (pin "1") (pinfunction "1_1") (pintype "passive"))
      (node (ref "R47") (pin "1") (pinfunction "1_1") (pintype "passive"))
      (node (ref "R54") (pin "1") (pinfunction "1_1") (pintype "passive"))
      (node (ref "R58") (pin "1") (pinfunction "1_1") (pintype "passive"))
      (node (ref "R63") (pin "1") (pinfunction "1_1") (pintype "passive"))
      (node (ref "R65") (pin "1") (pinfunction "1_1") (pintype "passive"))
      (node (ref "R67") (pin "1") (pinfunction "1_1") (pintype "passive"))
      (node (ref "R69") (pin "1") (pinfunction "1_1") (pintype "passive"))
      (node (ref "R71") (pin "1") (pinfunction "1_1") (pintype "passive"))
      (node (ref "R75") (pin "1") (pinfunction "1_1") (pintype "passive"))
      (node (ref "U1") (pin "2") (pinfunction "GND_2") (pintype "power_in"))
      (node (ref "U10") (pin "1") (pinfunction "GND_1") (pintype "power_in"))
      (node (ref "U10") (pin "11") (pinfunction "GND_11") (pintype "power_in"))
      (node (ref "U10") (pin "12") (pinfunction "GND_12") (pintype "power_in"))
      (node (ref "U10") (pin "16") (pinfunction "GND_16") (pintype "power_in"))
      (node (ref "U10") (pin "6") (pinfunction "LBO_6") (pintype "open_collector"))
      (node (ref "U10") (pin "7") (pinfunction "LBI_7") (pintype "input"))
      (node (ref "U10") (pin "9") (pinfunction "GND_9") (pintype "power_in"))
      (node (ref "U10") (pin "PAD") (pinfunction "GND_PAD") (pintype "power_in"))
      (node (ref "U11") (pin "2") (pinfunction "GND_2") (pintype "power_in"))
      (node (ref "U12") (pin "2") (pinfunction "GND_2") (pintype "power_in"))
      (node (ref "U2") (pin "6") (pinfunction "GND_6") (pintype "power_in"))
      (node (ref "U2") (pin "EPAD") (pinfunction "GND_EPAD") (pintype "power_in"))
      (node (ref "U6") (pin "7") (pinfunction "GND_7") (pintype "power_in"))
      (node (ref "U6") (pin "EPAD") (pinfunction "GND_EPAD") (pintype "power_in"))
      (node (ref "U7") (pin "23") (pinfunction "VSS_23") (pintype "power_in"))
      (node (ref "U7") (pin "35") (pinfunction "VSS_35") (pintype "power_in"))
      (node (ref "U7") (pin "47") (pinfunction "VSS_47") (pintype "power_in"))
      (node (ref "U7") (pin "8") (pinfunction "VSSA_8") (pintype "power_in"))
      (node (ref "X2") (pin "2") (pinfunction "SHIELD_2") (pintype "power_in"))
      (node (ref "X2") (pin "4") (pinfunction "SHIELD_4") (pintype "power_in"))
    )
    (net (code "28") (name "NRESET") (class "Default")
      (node (ref "J7") (pin "10") (pinfunction "NRST_10") (pintype "passive"))
      (node (ref "JP11") (pin "1") (pinfunction "1_1") (pintype "passive"))
      (node (ref "U7") (pin "7") (pinfunction "NRST_7") (pintype "bidirectional"))
    )
    (net (code "29") (name "Net-(C8-Pad1)") (class "Default")
      (node (ref "C8") (pin "1") (pinfunction "1_1") (pintype "passive"))
      (node (ref "R71") (pin "2") (pinfunction "2_2") (pintype "passive"))
      (node (ref "R72") (pin "2") (pinfunction "2_2") (pintype "passive"))
    )
    (net (code "30") (name "Net-(CM1-CENTER)") (class "Default")
      (node (ref "CM1") (pin "RF") (pinfunction "CENTER_RF") (pintype "passive"))
      (node (ref "J2") (pin "FEED") (pinfunction "SIGNAL_FEED") (pintype "bidirectional"))
    )
    (net (code "31") (name "Net-(CM2-CENTER)") (class "Default")
      (node (ref "CM2") (pin "RF") (pinfunction "CENTER_RF") (pintype "passive"))
      (node (ref "J3") (pin "FEED") (pinfunction "SIGNAL_FEED") (pintype "bidirectional"))
    )
    (net (code "32") (name "Net-(CM3-CENTER)") (class "Default")
      (node (ref "CM3") (pin "RF") (pinfunction "CENTER_RF") (pintype "passive"))
      (node (ref "J4") (pin "FEED") (pinfunction "SIGNAL_FEED") (pintype "bidirectional"))
    )
    (net (code "33") (name "Net-(D3-PadA)") (class "Default")
      (node (ref "D3") (pin "A") (pinfunction "A_A") (pintype "passive"))
      (node (ref "R3") (pin "1") (pinfunction "1_1") (pintype "passive"))
    )
    (net (code "34") (name "Net-(D5-PadA)") (class "Default")
      (node (ref "D5") (pin "A") (pinfunction "A_A") (pintype "passive"))
      (node (ref "R48") (pin "1") (pinfunction "1_1") (pintype "passive"))
    )
    (net (code "35") (name "Net-(D6-PadA)") (class "Default")
      (node (ref "D6") (pin "A") (pinfunction "A_A") (pintype "passive"))
      (node (ref "R17") (pin "1") (pinfunction "1_1") (pintype "passive"))
    )
    (net (code "36") (name "Net-(D7-PadA)") (class "Default")
      (node (ref "D7") (pin "A") (pinfunction "A_A") (pintype "passive"))
      (node (ref "R76") (pin "1") (pinfunction "1_1") (pintype "passive"))
    )
    (net (code "37") (name "Net-(J7-DEBUG-0)") (class "Default")
      (node (ref "J7") (pin "17") (pinfunction "DEBUG-0_17") (pintype "passive"))
      (node (ref "TP26") (pin "1") (pinfunction "1_1") (pintype "passive"))
    )
    (net (code "38") (name "Net-(J7-DEBUG-1)") (class "Default")
      (node (ref "J7") (pin "18") (pinfunction "DEBUG-1_18") (pintype "passive"))
      (node (ref "TP27") (pin "1") (pinfunction "1_1") (pintype "passive"))
    )
    (net (code "39") (name "Net-(J7-DEBUG-2)") (class "Default")
      (node (ref "J7") (pin "19") (pinfunction "DEBUG-2_19") (pintype "passive"))
      (node (ref "TP28") (pin "1") (pinfunction "1_1") (pintype "passive"))
    )
    (net (code "40") (name "Net-(J7-DEBUG-3)") (class "Default")
      (node (ref "J7") (pin "20") (pinfunction "DEBUG-3_20") (pintype "passive"))
      (node (ref "TP29") (pin "1") (pinfunction "1_1") (pintype "passive"))
    )
    (net (code "41") (name "Net-(J7-SWO)") (class "Default")
      (node (ref "J7") (pin "16") (pinfunction "SWO_16") (pintype "passive"))
      (node (ref "TP30") (pin "1") (pinfunction "1_1") (pintype "passive"))
    )
    (net (code "42") (name "Net-(L1-Pad1)") (class "Default")
      (node (ref "L1") (pin "1") (pinfunction "1_1") (pintype "passive"))
      (node (ref "U10") (pin "14") (pinfunction "SW_14") (pintype "output"))
      (node (ref "U10") (pin "15") (pinfunction "SW_15") (pintype "output"))
    )
    (net (code "43") (name "Net-(Q1A-G)") (class "Default")
      (node (ref "Q1") (pin "1") (pinfunction "G_1") (pintype "passive"))
      (node (ref "R77") (pin "2") (pinfunction "2_2") (pintype "passive"))
    )
    (net (code "44") (name "Net-(Q1A-S)") (class "Default")
      (node (ref "Q1") (pin "5") (pinfunction "S_5") (pintype "passive"))
      (node (ref "R60") (pin "2") (pinfunction "2_2") (pintype "passive"))
    )
    (net (code "45") (name "Net-(Q1B-G)") (class "Default")
      (node (ref "Q1") (pin "3") (pinfunction "G_3") (pintype "passive"))
      (node (ref "R81") (pin "2") (pinfunction "2_2") (pintype "passive"))
    )
    (net (code "46") (name "Net-(Q1B-S)") (class "Default")
      (node (ref "Q1") (pin "2") (pinfunction "S_2") (pintype "passive"))
      (node (ref "R80") (pin "2") (pinfunction "2_2") (pintype "passive"))
    )
    (net (code "47") (name "Net-(Q2-S)") (class "Default")
      (node (ref "Q2") (pin "4") (pinfunction "S_4") (pintype "passive"))
      (node (ref "R64") (pin "2") (pinfunction "2_2") (pintype "passive"))
      (node (ref "R70") (pin "2") (pinfunction "2_2") (pintype "passive"))
      (node (ref "U6") (pin "15") (pinfunction "RS-_15") (pintype "passive"))
    )
    (net (code "48") (name "Net-(Q7-G)") (class "Default")
      (node (ref "Q7") (pin "3") (pinfunction "G_3") (pintype "passive"))
      (node (ref "Q8") (pin "3") (pinfunction "D_3") (pintype "passive"))
      (node (ref "R62") (pin "1") (pinfunction "1_1") (pintype "passive"))
    )
    (net (code "49") (name "Net-(U2-IO6)") (class "Default")
      (node (ref "TP40") (pin "1") (pinfunction "1_1") (pintype "passive"))
      (node (ref "U2") (pin "11") (pinfunction "IO6_11") (pintype "bidirectional"))
    )
    (net (code "50") (name "Net-(U2-IO7)") (class "Default")
      (node (ref "TP36") (pin "1") (pinfunction "1_1") (pintype "passive"))
      (node (ref "U2") (pin "12") (pinfunction "IO7_12") (pintype "bidirectional"))
    )
    (net (code "51") (name "Net-(U2-~{RESET})") (class "Default")
      (node (ref "R61") (pin "1") (pinfunction "1_1") (pintype "passive"))
      (node (ref "U2") (pin "13") (pinfunction "~{RESET}_13") (pintype "input"))
    )
    (net (code "52") (name "Net-(U6-CIN1+)") (class "Default")
      (node (ref "R66") (pin "1") (pinfunction "1_1") (pintype "passive"))
      (node (ref "R67") (pin "2") (pinfunction "2_2") (pintype "passive"))
      (node (ref "TP15") (pin "1") (pinfunction "1_1") (pintype "passive"))
      (node (ref "U6") (pin "10") (pinfunction "CIN1+_10") (pintype "input"))
    )
    (net (code "53") (name "Net-(U6-CIN1-)") (class "Default")
      (node (ref "R68") (pin "1") (pinfunction "1_1") (pintype "passive"))
      (node (ref "R69") (pin "2") (pinfunction "2_2") (pintype "passive"))
      (node (ref "TP4") (pin "1") (pinfunction "1_1") (pintype "passive"))
      (node (ref "U6") (pin "11") (pinfunction "CIN1-_11") (pintype "input"))
    )
    (net (code "54") (name "Net-(U6-CIN2+)") (class "Default")
      (node (ref "R68") (pin "2") (pinfunction "2_2") (pintype "passive"))
      (node (ref "U6") (pin "12") (pinfunction "REF_12") (pintype "output"))
      (node (ref "U6") (pin "8") (pinfunction "CIN2+_8") (pintype "input"))
    )
    (net (code "55") (name "Net-(U6-INHIBIT)") (class "Default")
      (node (ref "R72") (pin "1") (pinfunction "1_1") (pintype "passive"))
      (node (ref "U6") (pin "5") (pinfunction "INHIBIT_5") (pintype "input"))
    )
    (net (code "56") (name "Net-(U6-IOUT)") (class "Default")
      (node (ref "R66") (pin "2") (pinfunction "2_2") (pintype "passive"))
      (node (ref "U6") (pin "14") (pinfunction "IOUT_14") (pintype "output"))
    )
    (net (code "57") (name "Net-(U6-RS+)") (class "Default")
      (node (ref "C1") (pin "1") (pinfunction "1_1") (pintype "passive"))
      (node (ref "Q7") (pin "1") (pinfunction "D_1") (pintype "passive"))
      (node (ref "Q7") (pin "2") (pinfunction "D_2") (pintype "passive"))
      (node (ref "Q7") (pin "5") (pinfunction "D_5") (pintype "passive"))
      (node (ref "Q7") (pin "6") (pinfunction "D_6") (pintype "passive"))
      (node (ref "R64") (pin "1") (pinfunction "1_1") (pintype "passive"))
      (node (ref "U6") (pin "16") (pinfunction "RS+_16") (pintype "passive"))
    )
    (net (code "58") (name "Net-(U7-PF0-OSC_IN)") (class "Default")
      (node (ref "C18") (pin "1") (pinfunction "1_1") (pintype "passive"))
      (node (ref "U7") (pin "5") (pinfunction "PF0-OSC_IN_5") (pintype "bidirectional"))
      (node (ref "X2") (pin "1") (pinfunction "1_1") (pintype "passive"))
    )
    (net (code "59") (name "Net-(U7-PF1-OSC_OUT)") (class "Default")
      (node (ref "C15") (pin "1") (pinfunction "1_1") (pintype "passive"))
      (node (ref "U7") (pin "6") (pinfunction "PF1-OSC_OUT_6") (pintype "bidirectional"))
      (node (ref "X2") (pin "3") (pinfunction "2_3") (pintype "passive"))
    )
    (net (code "60") (name "Net-(U10-PG)") (class "Default")
      (node (ref "TP32") (pin "1") (pinfunction "1_1") (pintype "passive"))
      (node (ref "U10") (pin "13") (pinfunction "PG_13") (pintype "open_collector"))
    )
    (net (code "61") (name "Net-(U10-SYNC)") (class "Default")
      (node (ref "R74") (pin "1") (pinfunction "1_1") (pintype "passive"))
      (node (ref "R75") (pin "2") (pinfunction "2_2") (pintype "passive"))
      (node (ref "TP33") (pin "1") (pinfunction "1_1") (pintype "passive"))
      (node (ref "U10") (pin "5") (pinfunction "SYNC_5") (pintype "input"))
    )
    (net (code "62") (name "Net-(U11-INP)") (class "Default")
      (node (ref "C23") (pin "1") (pinfunction "1_1") (pintype "passive"))
      (node (ref "R82") (pin "1") (pinfunction "1_1") (pintype "passive"))
      (node (ref "R83") (pin "1") (pinfunction "1_1") (pintype "passive"))
      (node (ref "U11") (pin "1") (pinfunction "INP_1") (pintype "input"))
    )
    (net (code "63") (name "Net-(U11-OUT)") (class "Default")
      (node (ref "R81") (pin "1") (pinfunction "1_1") (pintype "passive"))
      (node (ref "TP42") (pin "1") (pinfunction "1_1") (pintype "passive"))
      (node (ref "U11") (pin "4") (pinfunction "OUT_4") (pintype "output"))
    )
    (net (code "64") (name "Net-(U12-INP)") (class "Default")
      (node (ref "C22") (pin "1") (pinfunction "1_1") (pintype "passive"))
      (node (ref "R78") (pin "1") (pinfunction "1_1") (pintype "passive"))
      (node (ref "R79") (pin "1") (pinfunction "1_1") (pintype "passive"))
      (node (ref "U12") (pin "1") (pinfunction "INP_1") (pintype "input"))
    )
    (net (code "65") (name "Net-(U12-OUT)") (class "Default")
      (node (ref "R77") (pin "1") (pinfunction "1_1") (pintype "passive"))
      (node (ref "TP41") (pin "1") (pinfunction "1_1") (pintype "passive"))
      (node (ref "U12") (pin "4") (pinfunction "OUT_4") (pintype "output"))
    )
    (net (code "66") (name "ON{slash}~{OFF}") (class "Default")
      (node (ref "C17") (pin "1") (pinfunction "1_1") (pintype "passive"))
      (node (ref "Q8") (pin "1") (pinfunction "G_1") (pintype "passive"))
      (node (ref "R63") (pin "2") (pinfunction "2_2") (pintype "passive"))
      (node (ref "R76") (pin "2") (pinfunction "2_2") (pintype "passive"))
      (node (ref "TP21") (pin "1") (pinfunction "1_1") (pintype "passive"))
      (node (ref "U2") (pin "8") (pinfunction "IO3_8") (pintype "bidirectional"))
      (node (ref "U6") (pin "1") (pinfunction "VCC_1") (pintype "power_in"))
    )
    (net (code "67") (name "OPD_PWR") (class "Default")
      (node (ref "J6") (pin "15") (pinfunction "15_15") (pintype "passive"))
      (node (ref "J6") (pin "16") (pinfunction "16_16") (pintype "passive"))
      (node (ref "R24") (pin "1") (pinfunction "1_1") (pintype "passive"))
    )
    (net (code "68") (name "OPD_SCL") (class "Default")
      (node (ref "J6") (pin "13") (pinfunction "13_13") (pintype "passive"))
      (node (ref "J6") (pin "14") (pinfunction "14_14") (pintype "passive"))
      (node (ref "R80") (pin "1") (pinfunction "1_1") (pintype "passive"))
    )
    (net (code "69") (name "OPD_SDA") (class "Default")
      (node (ref "J6") (pin "11") (pinfunction "11_11") (pintype "passive"))
      (node (ref "J6") (pin "12") (pinfunction "12_12") (pintype "passive"))
      (node (ref "R60") (pin "1") (pinfunction "1_1") (pintype "passive"))
    )
    (net (code "70") (name "PA0") (class "Default")
      (node (ref "JP8") (pin "7") (pinfunction "7_7") (pintype "passive"))
      (node (ref "R48") (pin "2") (pinfunction "2_2") (pintype "passive"))
      (node (ref "U7") (pin "10") (pinfunction "PA0_10") (pintype "bidirectional"))
    )
    (net (code "71") (name "PA1") (class "Default")
      (node (ref "JP8") (pin "9") (pinfunction "9_9") (pintype "passive"))
      (node (ref "U7") (pin "11") (pinfunction "PA1_11") (pintype "bidirectional"))
    )
    (net (code "72") (name "PA2{slash}USART2_TX") (class "Default")
      (node (ref "J7") (pin "13") (pinfunction "CARD-TX_13") (pintype "passive"))
      (node (ref "JP8") (pin "11") (pinfunction "11_11") (pintype "passive"))
      (node (ref "U7") (pin "12") (pinfunction "PA2_12") (pintype "bidirectional"))
    )
    (net (code "73") (name "PA3{slash}USART2_RX") (class "Default")
      (node (ref "J7") (pin "12") (pinfunction "CARD-RX_12") (pintype "passive"))
      (node (ref "JP8") (pin "13") (pinfunction "13_13") (pintype "passive"))
      (node (ref "U7") (pin "13") (pinfunction "PA3_13") (pintype "bidirectional"))
    )
    (net (code "74") (name "PA4") (class "Default")
      (node (ref "JP8") (pin "15") (pinfunction "15_15") (pintype "passive"))
      (node (ref "U7") (pin "14") (pinfunction "PA4_14") (pintype "bidirectional"))
    )
    (net (code "75") (name "PA5{slash}SPI1_SCK") (class "Default")
      (node (ref "JP8") (pin "17") (pinfunction "17_17") (pintype "passive"))
      (node (ref "U7") (pin "15") (pinfunction "PA5_15") (pintype "bidirectional"))
    )
    (net (code "76") (name "PA6{slash}SPI1_MISO") (class "Default")
      (node (ref "JP8") (pin "2") (pinfunction "2_2") (pintype "passive"))
      (node (ref "U7") (pin "16") (pinfunction "PA6_16") (pintype "bidirectional"))
    )
    (net (code "77") (name "PA7{slash}SPI1_MOSI") (class "Default")
      (node (ref "JP8") (pin "4") (pinfunction "4_4") (pintype "passive"))
      (node (ref "U7") (pin "17") (pinfunction "PA7_17") (pintype "bidirectional"))
    )
    (net (code "78") (name "PA8") (class "Default")
      (node (ref "JP8") (pin "6") (pinfunction "6_6") (pintype "passive"))
      (node (ref "U7") (pin "29") (pinfunction "PA8_29") (pintype "bidirectional"))
    )
    (net (code "79") (name "PA9{slash}CAN_SILENT") (class "Default")
      (node (ref "JP8") (pin "8") (pinfunction "8_8") (pintype "passive"))
      (node (ref "U1") (pin "8") (pinfunction "S_8") (pintype "input"))
      (node (ref "U7") (pin "30") (pinfunction "PA9_30") (pintype "bidirectional"))
    )
    (net (code "80") (name "PA15") (class "Default")
      (node (ref "JP8") (pin "16") (pinfunction "16_16") (pintype "passive"))
      (node (ref "U7") (pin "38") (pinfunction "PA15_38") (pintype "bidirectional"))
    )
    (net (code "81") (name "PB0{slash}POUTPROT") (class "Default")
      (node (ref "JP11") (pin "9") (pinfunction "9_9") (pintype "passive"))
      (node (ref "R49") (pin "2") (pinfunction "2_2") (pintype "passive"))
      (node (ref "U7") (pin "18") (pinfunction "PB0_18") (pintype "bidirectional"))
    )
    (net (code "82") (name "PB1") (class "Default")
      (node (ref "JP11") (pin "11") (pinfunction "11_11") (pintype "passive"))
      (node (ref "U7") (pin "19") (pinfunction "PB1_19") (pintype "bidirectional"))
    )
    (net (code "83") (name "PB2") (class "Default")
      (node (ref "JP11") (pin "13") (pinfunction "13_13") (pintype "passive"))
      (node (ref "U7") (pin "20") (pinfunction "PB2_20") (pintype "bidirectional"))
    )
    (net (code "84") (name "PB3") (class "Default")
      (node (ref "JP11") (pin "15") (pinfunction "15_15") (pintype "passive"))
      (node (ref "U7") (pin "39") (pinfunction "PB3_39") (pintype "bidirectional"))
    )
    (net (code "85") (name "PB4") (class "Default")
      (node (ref "JP11") (pin "17") (pinfunction "17_17") (pintype "passive"))
      (node (ref "U7") (pin "40") (pinfunction "PB4_40") (pintype "bidirectional"))
    )
    (net (code "86") (name "PB5") (class "Default")
      (node (ref "JP11") (pin "19") (pinfunction "19_19") (pintype "passive"))
      (node (ref "U7") (pin "41") (pinfunction "PB5_41") (pintype "bidirectional"))
    )
    (net (code "87") (name "PB6{slash}SCL") (class "Default")
      (node (ref "JP11") (pin "2") (pinfunction "2_2") (pintype "passive"))
      (node (ref "R50") (pin "1") (pinfunction "1_1") (pintype "passive"))
      (node (ref "U2") (pin "4") (pinfunction "IO0_4") (pintype "bidirectional"))
      (node (ref "U7") (pin "42") (pinfunction "PB6_42") (pintype "bidirectional"))
    )
    (net (code "88") (name "PB7{slash}SDA") (class "Default")
      (node (ref "JP11") (pin "4") (pinfunction "4_4") (pintype "passive"))
      (node (ref "R51") (pin "1") (pinfunction "1_1") (pintype "passive"))
      (node (ref "U2") (pin "5") (pinfunction "IO1_5") (pintype "bidirectional"))
      (node (ref "U7") (pin "43") (pinfunction "PB7_43") (pintype "bidirectional"))
    )
    (net (code "89") (name "PB8") (class "Default")
      (node (ref "JP11") (pin "6") (pinfunction "6_6") (pintype "passive"))
      (node (ref "U7") (pin "45") (pinfunction "PB8_45") (pintype "bidirectional"))
    )
    (net (code "90") (name "PB9") (class "Default")
      (node (ref "JP11") (pin "8") (pinfunction "8_8") (pintype "passive"))
      (node (ref "U7") (pin "46") (pinfunction "PB9_46") (pintype "bidirectional"))
    )
    (net (code "91") (name "PB10") (class "Default")
      (node (ref "JP11") (pin "10") (pinfunction "10_10") (pintype "passive"))
      (node (ref "U7") (pin "21") (pinfunction "PB10_21") (pintype "bidirectional"))
    )
    (net (code "92") (name "PB11") (class "Default")
      (node (ref "JP11") (pin "12") (pinfunction "12_12") (pintype "passive"))
      (node (ref "U7") (pin "22") (pinfunction "PB11_22") (pintype "bidirectional"))
    )
    (net (code "93") (name "PB12") (class "Default")
      (node (ref "JP11") (pin "14") (pinfunction "14_14") (pintype "passive"))
      (node (ref "U7") (pin "25") (pinfunction "PB12_25") (pintype "bidirectional"))
    )
    (net (code "94") (name "PB13") (class "Default")
      (node (ref "JP11") (pin "16") (pinfunction "16_16") (pintype "passive"))
      (node (ref "U7") (pin "26") (pinfunction "PB13_26") (pintype "bidirectional"))
    )
    (net (code "95") (name "PB14") (class "Default")
      (node (ref "JP11") (pin "18") (pinfunction "18_18") (pintype "passive"))
      (node (ref "U7") (pin "27") (pinfunction "PB14_27") (pintype "bidirectional"))
    )
    (net (code "96") (name "PB15") (class "Default")
      (node (ref "JP11") (pin "20") (pinfunction "20_20") (pintype "passive"))
      (node (ref "U7") (pin "28") (pinfunction "PB15_28") (pintype "bidirectional"))
    )
    (net (code "97") (name "PC13") (class "Default")
      (node (ref "JP8") (pin "1") (pinfunction "1_1") (pintype "passive"))
      (node (ref "U7") (pin "2") (pinfunction "PC13_2") (pintype "bidirectional"))
    )
    (net (code "98") (name "PC14") (class "Default")
      (node (ref "JP8") (pin "3") (pinfunction "3_3") (pintype "passive"))
      (node (ref "U7") (pin "3") (pinfunction "PC14-OSC32_IN_3") (pintype "bidirectional"))
    )
    (net (code "99") (name "PC15") (class "Default")
      (node (ref "JP8") (pin "5") (pinfunction "5_5") (pintype "passive"))
      (node (ref "U7") (pin "4") (pinfunction "PC15-OSC32_OUT_4") (pintype "bidirectional"))
    )
    (net (code "100") (name "PEN-SCL-FILT") (class "Default")
      (node (ref "Q1") (pin "4") (pinfunction "D_4") (pintype "passive"))
      (node (ref "R40") (pin "1") (pinfunction "1_1") (pintype "passive"))
      (node (ref "R53") (pin "1") (pinfunction "1_1") (pintype "passive"))
      (node (ref "R57") (pin "1") (pinfunction "1_1") (pintype "passive"))
      (node (ref "R82") (pin "2") (pinfunction "2_2") (pintype "passive"))
      (node (ref "TP37") (pin "1") (pinfunction "1_1") (pintype "passive"))
      (node (ref "U2") (pin "15") (pinfunction "SCL_15") (pintype "input"))
    )
    (net (code "101") (name "PEN-SDA-FILT") (class "Default")
      (node (ref "Q1") (pin "6") (pinfunction "D_6") (pintype "passive"))
      (node (ref "R46") (pin "2") (pinfunction "2_2") (pintype "passive"))
      (node (ref "R55") (pin "2") (pinfunction "2_2") (pintype "passive"))
      (node (ref "R59") (pin "2") (pinfunction "2_2") (pintype "passive"))
      (node (ref "R78") (pin "2") (pinfunction "2_2") (pintype "passive"))
      (node (ref "TP38") (pin "1") (pinfunction "1_1") (pintype "passive"))
      (node (ref "U2") (pin "16") (pinfunction "SDA_16") (pintype "bidirectional"))
    )
    (net (code "102") (name "POUT") (class "Default")
      (node (ref "R49") (pin "1") (pinfunction "1_1") (pintype "passive"))
      (node (ref "TP2") (pin "1") (pinfunction "1_1") (pintype "passive"))
      (node (ref "U6") (pin "13") (pinfunction "POUT_13") (pintype "output"))
    )
    (net (code "103") (name "SPARE1") (class "Default")
      (node (ref "J6") (pin "10") (pinfunction "10_10") (pintype "passive"))
      (node (ref "J6") (pin "9") (pinfunction "9_9") (pintype "passive"))
      (node (ref "JP2") (pin "5") (pinfunction "5_5") (pintype "passive"))
    )
    (net (code "104") (name "SPARE2") (class "Default")
      (node (ref "J6") (pin "7") (pinfunction "7_7") (pintype "passive"))
      (node (ref "J6") (pin "8") (pinfunction "8_8") (pintype "passive"))
      (node (ref "JP2") (pin "4") (pinfunction "4_4") (pintype "passive"))
    )
    (net (code "105") (name "SPARE3") (class "Default")
      (node (ref "J6") (pin "5") (pinfunction "5_5") (pintype "passive"))
      (node (ref "J6") (pin "6") (pinfunction "6_6") (pintype "passive"))
      (node (ref "JP2") (pin "3") (pinfunction "3_3") (pintype "passive"))
    )
    (net (code "106") (name "SPARE4") (class "Default")
      (node (ref "J6") (pin "3") (pinfunction "3_3") (pintype "passive"))
      (node (ref "J6") (pin "4") (pinfunction "4_4") (pintype "passive"))
      (node (ref "JP2") (pin "2") (pinfunction "2_2") (pintype "passive"))
    )
    (net (code "107") (name "SPARE5") (class "Default")
      (node (ref "J6") (pin "1") (pinfunction "1_1") (pintype "passive"))
      (node (ref "J6") (pin "2") (pinfunction "2_2") (pintype "passive"))
      (node (ref "JP2") (pin "1") (pinfunction "1_1") (pintype "passive"))
    )
    (net (code "108") (name "SWCLK") (class "Default")
      (node (ref "J7") (pin "15") (pinfunction "SWCLK_15") (pintype "passive"))
      (node (ref "JP11") (pin "7") (pinfunction "7_7") (pintype "passive"))
      (node (ref "U7") (pin "37") (pinfunction "PA14-SWCLK_37") (pintype "bidirectional"))
    )
    (net (code "109") (name "SWDIO") (class "Default")
      (node (ref "J7") (pin "14") (pinfunction "SWDIO_14") (pintype "passive"))
      (node (ref "JP11") (pin "5") (pinfunction "5_5") (pintype "passive"))
      (node (ref "U7") (pin "34") (pinfunction "PA13-SWDIO_34") (pintype "bidirectional"))
    )
    (net (code "110") (name "VBUS") (class "Default")
      (node (ref "J6") (pin "21") (pinfunction "21_21") (pintype "passive"))
      (node (ref "J6") (pin "22") (pinfunction "22_22") (pintype "passive"))
      (node (ref "J6") (pin "23") (pinfunction "23_23") (pintype "passive"))
      (node (ref "J6") (pin "24") (pinfunction "24_24") (pintype "passive"))
      (node (ref "J6") (pin "25") (pinfunction "25_25") (pintype "passive"))
      (node (ref "J6") (pin "26") (pinfunction "26_26") (pintype "passive"))
      (node (ref "JP10") (pin "1") (pinfunction "1_1") (pintype "passive"))
      (node (ref "JP10") (pin "2") (pinfunction "2_2") (pintype "passive"))
      (node (ref "JP10") (pin "3") (pinfunction "3_3") (pintype "passive"))
      (node (ref "JP10") (pin "4") (pinfunction "4_4") (pintype "passive"))
      (node (ref "Q7") (pin "4") (pinfunction "S_4") (pintype "passive"))
      (node (ref "R62") (pin "2") (pinfunction "2_2") (pintype "passive"))
    )
    (net (code "111") (name "VBUSP") (class "Default")
      (node (ref "C11") (pin "1") (pinfunction "1_1") (pintype "passive"))
      (node (ref "C8") (pin "2") (pinfunction "2_2") (pintype "passive"))
      (node (ref "C9") (pin "1") (pinfunction "1_1") (pintype "passive"))
      (node (ref "J7") (pin "1") (pinfunction "VBUSP_1") (pintype "passive"))
      (node (ref "J7") (pin "2") (pinfunction "VBUSP_2") (pintype "passive"))
      (node (ref "Q2") (pin "1") (pinfunction "D_1") (pintype "passive"))
      (node (ref "Q2") (pin "2") (pinfunction "D_2") (pintype "passive"))
      (node (ref "Q2") (pin "5") (pinfunction "D_5") (pintype "passive"))
      (node (ref "Q2") (pin "6") (pinfunction "D_6") (pintype "passive"))
      (node (ref "R3") (pin "2") (pinfunction "2_2") (pintype "passive"))
      (node (ref "R74") (pin "2") (pinfunction "2_2") (pintype "passive"))
      (node (ref "TP31") (pin "1") (pinfunction "1_1") (pintype "passive"))
      (node (ref "U10") (pin "2") (pinfunction "VIN_2") (pintype "power_in"))
      (node (ref "U10") (pin "3") (pinfunction "VIN_3") (pintype "power_in"))
      (node (ref "U10") (pin "4") (pinfunction "EN_4") (pintype "input"))
      (node (ref "U10") (pin "8") (pinfunction "VIN_8") (pintype "power_in"))
    )
    (net (code "112") (name "VPD") (class "Default")
      (node (ref "C3") (pin "2") (pinfunction "2_2") (pintype "passive"))
      (node (ref "R24") (pin "2") (pinfunction "2_2") (pintype "passive"))
      (node (ref "R39") (pin "2") (pinfunction "2_2") (pintype "passive"))
      (node (ref "R52") (pin "2") (pinfunction "2_2") (pintype "passive"))
      (node (ref "R56") (pin "2") (pinfunction "2_2") (pintype "passive"))
      (node (ref "R61") (pin "2") (pinfunction "2_2") (pintype "passive"))
      (node (ref "R73") (pin "2") (pinfunction "2_2") (pintype "passive"))
      (node (ref "R79") (pin "2") (pinfunction "2_2") (pintype "passive"))
      (node (ref "R83") (pin "2") (pinfunction "2_2") (pintype "passive"))
      (node (ref "TP35") (pin "1") (pinfunction "1_1") (pintype "passive"))
      (node (ref "U11") (pin "5") (pinfunction "VDD_5") (pintype "power_in"))
      (node (ref "U12") (pin "5") (pinfunction "VDD_5") (pintype "power_in"))
      (node (ref "U2") (pin "14") (pinfunction "V+_14") (pintype "power_in"))
    )
    (net (code "113") (name "unconnected-(J7-DEVICE-D+-Pad4)") (class "Default")
      (node (ref "J7") (pin "4") (pinfunction "DEVICE-D+_4") (pintype "passive"))
    )
    (net (code "114") (name "unconnected-(J7-DEVICE-D--Pad5)") (class "Default")
      (node (ref "J7") (pin "5") (pinfunction "DEVICE-D-_5") (pintype "passive"))
    )
    (net (code "115") (name "unconnected-(J7-HOST-D+-Pad7)") (class "Default")
      (node (ref "J7") (pin "7") (pinfunction "HOST-D+_7") (pintype "passive"))
    )
    (net (code "116") (name "unconnected-(J7-HOST-D--Pad8)") (class "Default")
      (node (ref "J7") (pin "8") (pinfunction "HOST-D-_8") (pintype "passive"))
    )
    (net (code "117") (name "unconnected-(JP2-Pad6)") (class "Default")
      (node (ref "JP2") (pin "6") (pinfunction "6_6") (pintype "passive"))
    )
    (net (code "118") (name "unconnected-(JP8-Pad18)") (class "Default")
      (node (ref "JP8") (pin "18") (pinfunction "18_18") (pintype "passive"))
    )
    (net (code "119") (name "unconnected-(JP8-Pad20)") (class "Default")
      (node (ref "JP8") (pin "20") (pinfunction "20_20") (pintype "passive"))
    )
    (net (code "120") (name "~{FAULT}") (class "Default")
      (node (ref "Q9") (pin "3") (pinfunction "D_3") (pintype "passive"))
      (node (ref "R73") (pin "1") (pinfunction "1_1") (pintype "passive"))
      (node (ref "TP24") (pin "1") (pinfunction "1_1") (pintype "passive"))
      (node (ref "U2") (pin "7") (pinfunction "IO2_7") (pintype "bidirectional"))
    )
    (net (code "121") (name "~{SD}") (class "Default")
      (node (ref "J6") (pin "39") (pinfunction "39_39") (pintype "passive"))
      (node (ref "J6") (pin "40") (pinfunction "40_40") (pintype "passive"))
      (node (ref "JP10") (pin "10") (pinfunction "10_10") (pintype "passive"))
      (node (ref "JP10") (pin "9") (pinfunction "9_9") (pintype "passive"))
    )
  )
)
